# Sheet1.net
KiCad netlist of a schematic drawn in Altium Designer
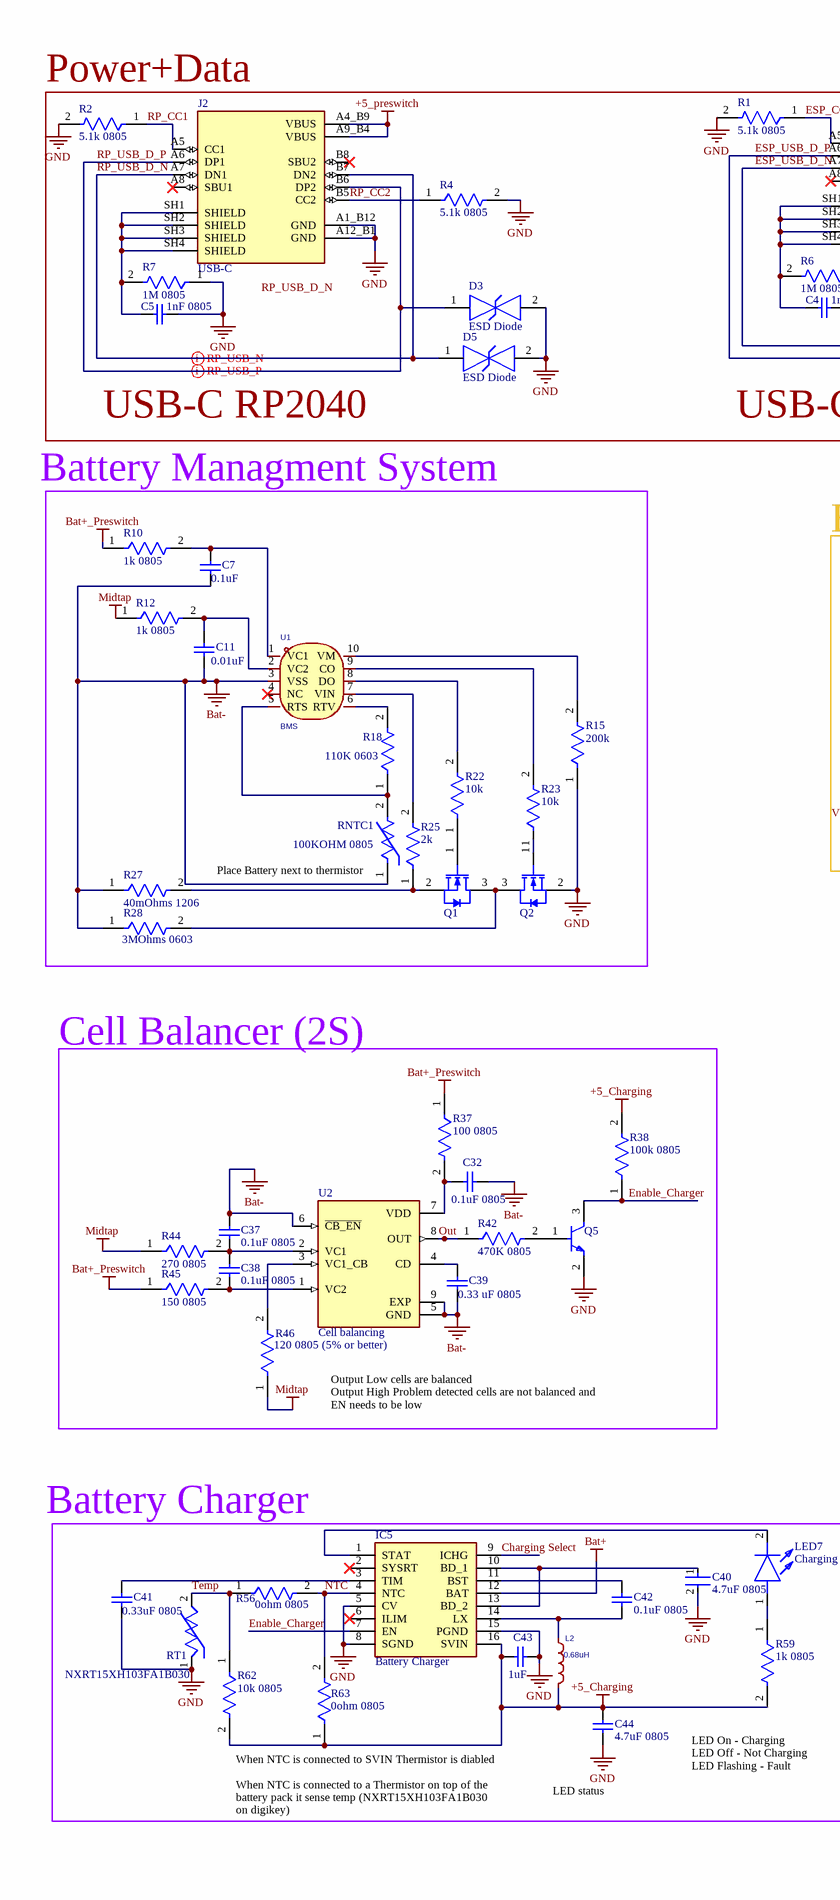
[diagram p0: Sheet1.SchDoc, left]
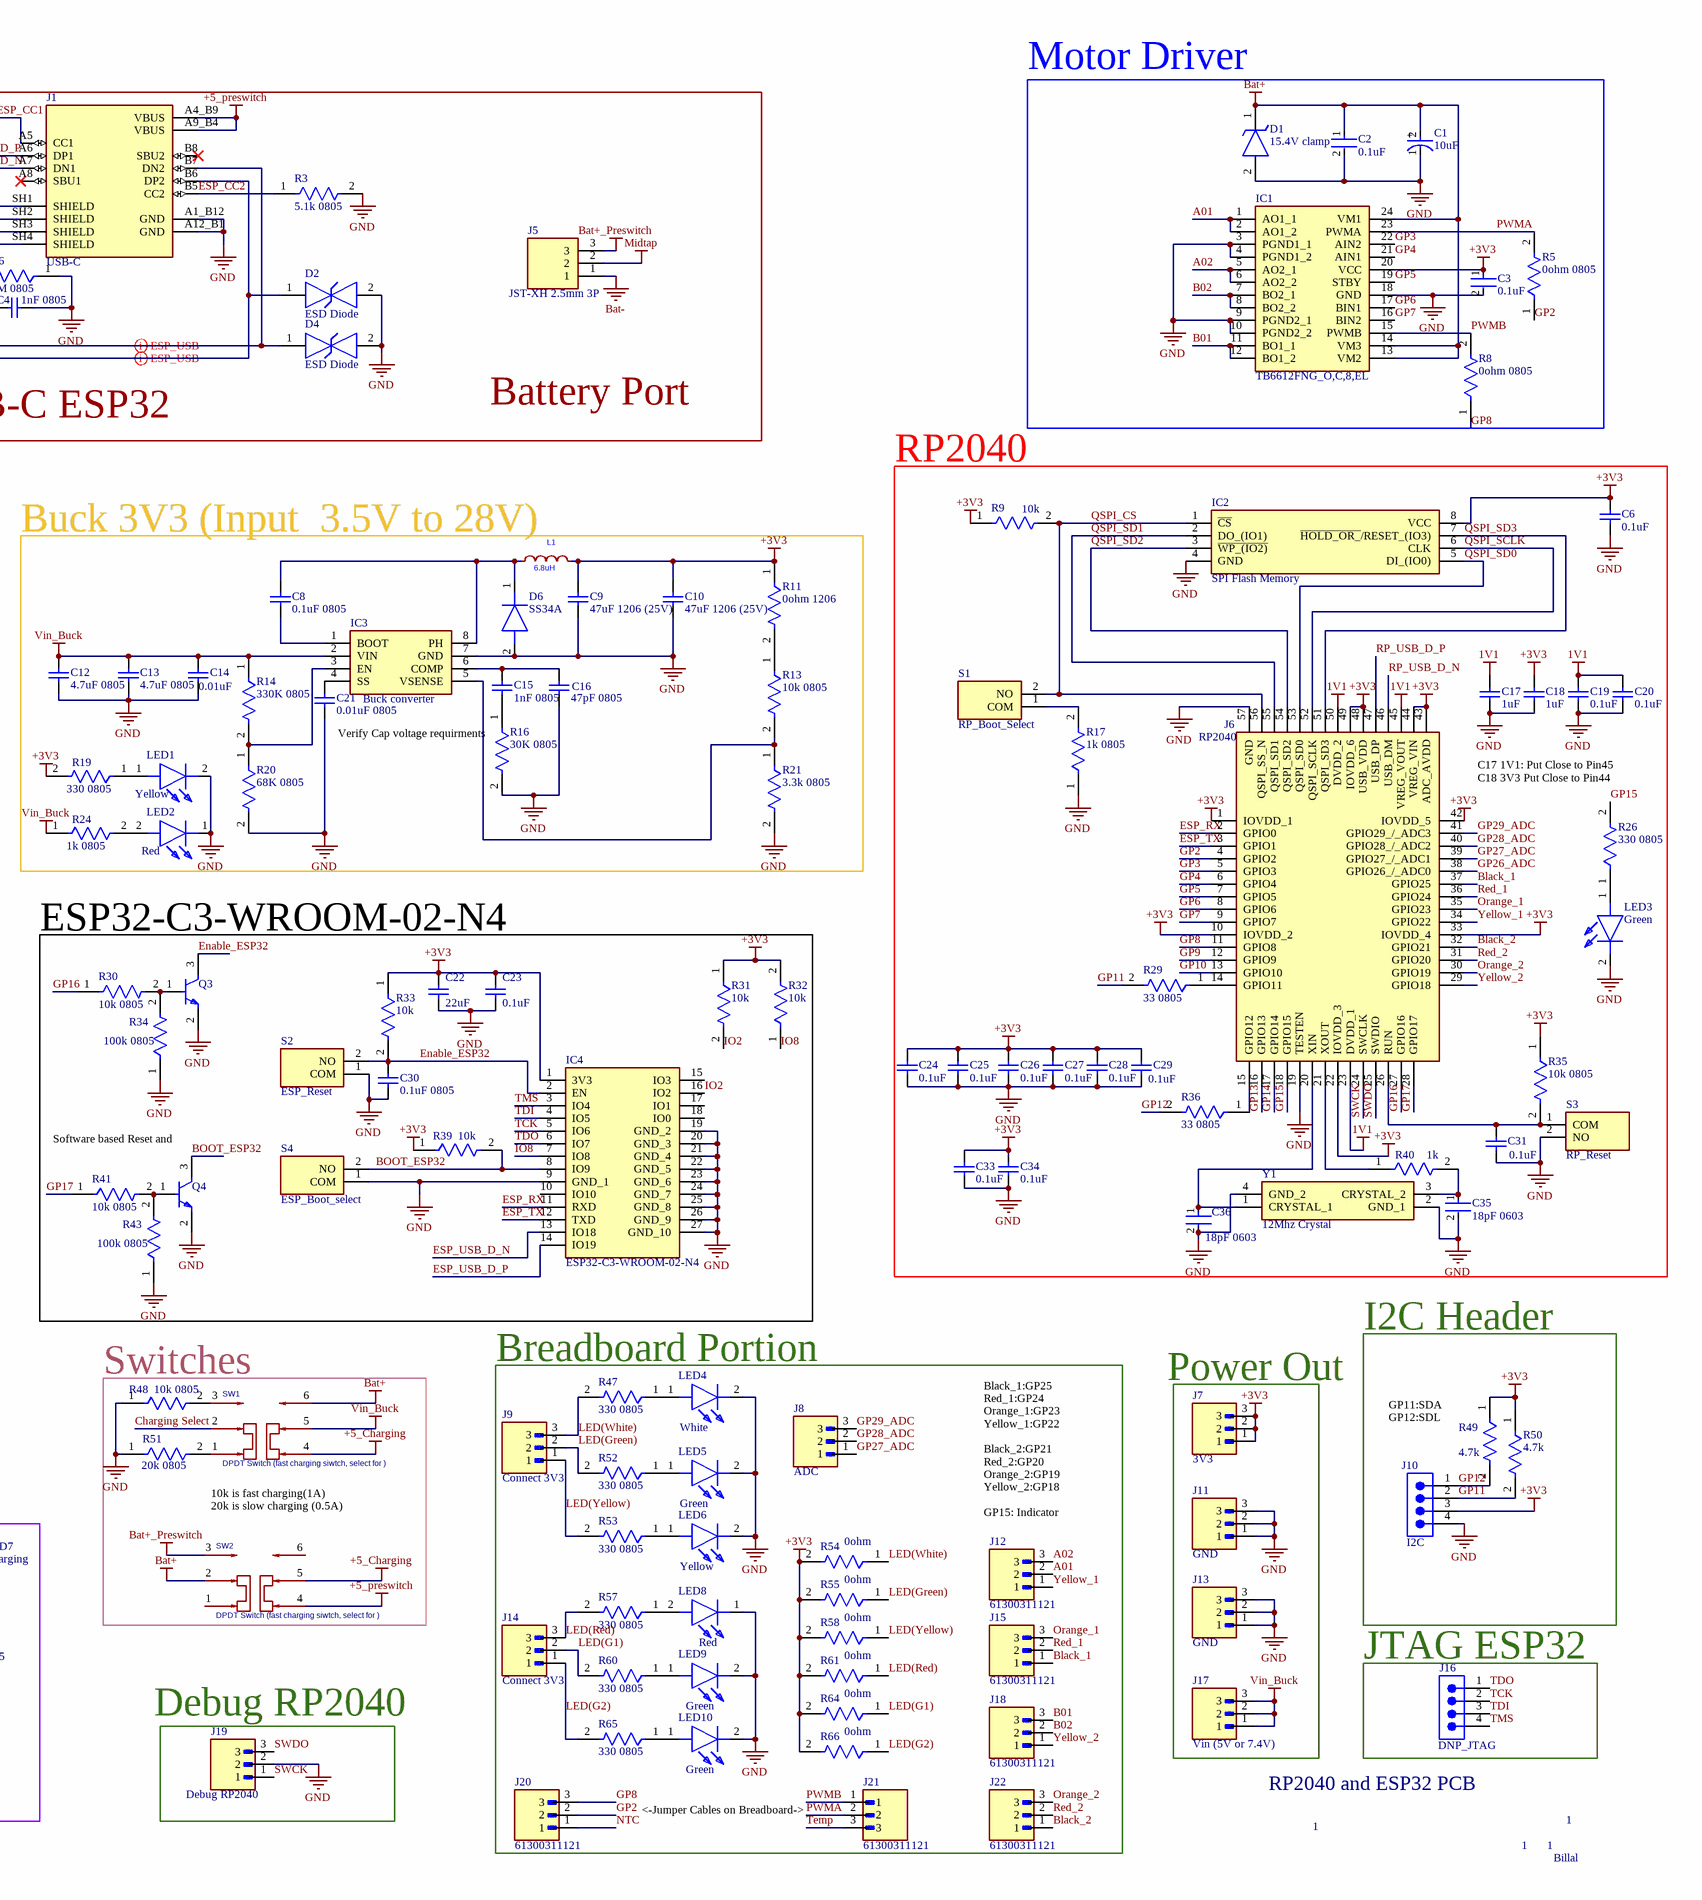
[diagram p1: Sheet1.SchDoc, right]

(export (version "E")
  (design (tool "Eeschema 10.0.6"))
  (components
    (comp (ref "C1")
      (value "10uF")
      (footprint "FP-TAJA-MFG")
      (description "C7171")
      (fields (field (name "VOLTAGE") "16V") (field (name "TOLERANCE") "10%"))
      (libsource (lib "Altium Content Vault") (part "203bc49f2ac43e59fd269a8c329ed05"))
    )
    (comp (ref "C2")
      (value "0.1uF")
      (footprint "FP-CL779-IPC_C")
      (description "C307331")
      (libsource (lib "Altium Content Vault") (part "b4654b650e69147ec39a6b967a45e02"))
    )
    (comp (ref "C3")
      (value "0.1uF")
      (footprint "FP-CL779-IPC_C")
      (description "C307331")
      (libsource (lib "Altium Content Vault") (part "b4654b650e69147ec39a6b967a45e02"))
    )
    (comp (ref "C4")
      (value "1nF 0805")
      (footprint "CAPC2013X94X50LL20T25")
      (description "C46653")
      (fields
        (field (name "PART NUMBER") "08051C102KAT4A")
        (field (name "MANUFACTURER") "AVX Interconnect / Elco")
      )
      (libsource (lib "Altium Content Vault") (part "CAP"))
    )
    (comp (ref "C5")
      (value "1nF 0805")
      (footprint "CAPC2013X94X50LL20T25")
      (description "C46653")
      (fields
        (field (name "PART NUMBER") "08051C102KAT4A")
        (field (name "MANUFACTURER") "AVX Interconnect / Elco")
      )
      (libsource (lib "Altium Content Vault") (part "CAP"))
    )
    (comp (ref "C6")
      (value "0.1uF")
      (footprint "CAPC2013X94X50LL20T25")
      (description "C28233")
      (fields
        (field (name "PART NUMBER") "08051C102KAT4A")
        (field (name "MANUFACTURER") "AVX Interconnect / Elco")
      )
      (libsource (lib "Altium Content Vault") (part "CAP"))
    )
    (comp (ref "C7")
      (value "0.1uF")
      (footprint "CAPC2013X94X50LL20T25")
      (description "C28233")
      (fields
        (field (name "PART NUMBER") "08051C102KAT4A")
        (field (name "MANUFACTURER") "AVX Interconnect / Elco")
      )
      (libsource (lib "Altium Content Vault") (part "CAP"))
    )
    (comp (ref "C8")
      (value "0.1uF 0805")
      (footprint "CAPC2013X94X50LL20T25")
      (description "C28233")
      (fields
        (field (name "PART NUMBER") "08051C102KAT4A")
        (field (name "MANUFACTURER") "AVX Interconnect / Elco")
      )
      (libsource (lib "Altium Content Vault") (part "CAP"))
    )
    (comp (ref "C9")
      (value "47uF 1206 (25V)")
      (footprint "CAPC1206(3216)190_N")
      (description "C6119973")
      (fields (field (name "TOLERANCE") "Â±20%"))
      (libsource (lib "Altium Content Vault") (part "CAP"))
    )
    (comp (ref "C10")
      (value "47uF 1206 (25V)")
      (footprint "CAPC1206(3216)190_N")
      (description "C6119973")
      (fields (field (name "TOLERANCE") "Â±20%"))
      (libsource (lib "Altium Content Vault") (part "CAP"))
    )
    (comp (ref "C11")
      (value "0.01uF")
      (footprint "CAPC2013X94X50LL20T25")
      (description "C1710")
      (fields
        (field (name "PART NUMBER") "08051C102KAT4A")
        (field (name "MANUFACTURER") "AVX Interconnect / Elco")
      )
      (libsource (lib "Altium Content Vault") (part "CAP"))
    )
    (comp (ref "C12")
      (value "4.7uF 0805")
      (footprint "CAPC2013X94X50LL20T25")
      (description "C1779")
      (fields
        (field (name "PART NUMBER") "08051C102KAT4A")
        (field (name "MANUFACTURER") "AVX Interconnect / Elco")
      )
      (libsource (lib "Altium Content Vault") (part "CAP"))
    )
    (comp (ref "C13")
      (value "4.7uF 0805")
      (footprint "CAPC2013X94X50LL20T25")
      (description "C1779")
      (fields
        (field (name "PART NUMBER") "08051C102KAT4A")
        (field (name "MANUFACTURER") "AVX Interconnect / Elco")
      )
      (libsource (lib "Altium Content Vault") (part "CAP"))
    )
    (comp (ref "C14")
      (value "0.01uF")
      (footprint "CAPC2013X94X50LL20T25")
      (description "C1710")
      (fields
        (field (name "PART NUMBER") "08051C102KAT4A")
        (field (name "MANUFACTURER") "AVX Interconnect / Elco")
      )
      (libsource (lib "Altium Content Vault") (part "CAP"))
    )
    (comp (ref "C15")
      (value "1nF 0805")
      (footprint "CAPC2013X94X50LL20T25")
      (description "C46653")
      (fields
        (field (name "PART NUMBER") "08051C102KAT4A")
        (field (name "MANUFACTURER") "AVX Interconnect / Elco")
      )
      (libsource (lib "Altium Content Vault") (part "CAP"))
    )
    (comp (ref "C16")
      (value "47pF 0805")
      (footprint "CAPC2013X94X50LL20T25")
      (description "C14857")
      (fields
        (field (name "PART NUMBER") "08051C102KAT4A")
        (field (name "MANUFACTURER") "AVX Interconnect / Elco")
      )
      (libsource (lib "Altium Content Vault") (part "CAP"))
    )
    (comp (ref "C17")
      (value "1uF")
      (footprint "CAPC2013X94X50LL20T25")
      (description "C28323\r\nPut Close to Pin45")
      (fields
        (field (name "PART NUMBER") "08051C102KAT4A")
        (field (name "MANUFACTURER") "AVX Interconnect / Elco")
      )
      (libsource (lib "Altium Content Vault") (part "CAP"))
    )
    (comp (ref "C18")
      (value "1uF")
      (footprint "CAPC2013X94X50LL20T25")
      (description "C28323\r\nPut Close to Pin44")
      (fields
        (field (name "PART NUMBER") "08051C102KAT4A")
        (field (name "MANUFACTURER") "AVX Interconnect / Elco")
      )
      (libsource (lib "Altium Content Vault") (part "CAP"))
    )
    (comp (ref "C19")
      (value "0.1uF")
      (footprint "CAPC2013X94X50LL20T25")
      (description "C28233")
      (fields
        (field (name "PART NUMBER") "08051C102KAT4A")
        (field (name "MANUFACTURER") "AVX Interconnect / Elco")
      )
      (libsource (lib "Altium Content Vault") (part "CAP"))
    )
    (comp (ref "C20")
      (value "0.1uF")
      (footprint "CAPC2013X94X50LL20T25")
      (description "C28233")
      (fields
        (field (name "PART NUMBER") "08051C102KAT4A")
        (field (name "MANUFACTURER") "AVX Interconnect / Elco")
      )
      (libsource (lib "Altium Content Vault") (part "CAP"))
    )
    (comp (ref "C21")
      (value "0.01uF 0805")
      (footprint "CAPC2013X94X50LL20T25")
      (description "C1710")
      (fields
        (field (name "PART NUMBER") "08051C102KAT4A")
        (field (name "MANUFACTURER") "AVX Interconnect / Elco")
      )
      (libsource (lib "Altium Content Vault") (part "CAP"))
    )
    (comp (ref "C22")
      (value "22uF")
      (footprint "CAPC2013X94X50LL20T25")
      (description "C45783")
      (fields
        (field (name "PART NUMBER") "08051C102KAT4A")
        (field (name "MANUFACTURER") "AVX Interconnect / Elco")
      )
      (libsource (lib "Altium Content Vault") (part "CAP"))
    )
    (comp (ref "C23")
      (value "0.1uF")
      (footprint "CAPC2013X94X50LL20T25")
      (description "C28233")
      (fields
        (field (name "PART NUMBER") "08051C102KAT4A")
        (field (name "MANUFACTURER") "AVX Interconnect / Elco")
      )
      (libsource (lib "Altium Content Vault") (part "CAP"))
    )
    (comp (ref "C24")
      (value "0.1uF")
      (footprint "CAPC2013X94X50LL20T25")
      (description "C28233")
      (fields
        (field (name "PART NUMBER") "08051C102KAT4A")
        (field (name "MANUFACTURER") "AVX Interconnect / Elco")
      )
      (libsource (lib "Altium Content Vault") (part "CAP"))
    )
    (comp (ref "C25")
      (value "0.1uF")
      (footprint "CAPC2013X94X50LL20T25")
      (description "C28233")
      (fields
        (field (name "PART NUMBER") "08051C102KAT4A")
        (field (name "MANUFACTURER") "AVX Interconnect / Elco")
      )
      (libsource (lib "Altium Content Vault") (part "CAP"))
    )
    (comp (ref "C26")
      (value "0.1uF")
      (footprint "CAPC2013X94X50LL20T25")
      (description "C28233")
      (fields
        (field (name "PART NUMBER") "08051C102KAT4A")
        (field (name "MANUFACTURER") "AVX Interconnect / Elco")
      )
      (libsource (lib "Altium Content Vault") (part "CAP"))
    )
    (comp (ref "C27")
      (value "0.1uF")
      (footprint "CAPC2013X94X50LL20T25")
      (description "C28233")
      (fields
        (field (name "PART NUMBER") "08051C102KAT4A")
        (field (name "MANUFACTURER") "AVX Interconnect / Elco")
      )
      (libsource (lib "Altium Content Vault") (part "CAP"))
    )
    (comp (ref "C28")
      (value "0.1uF")
      (footprint "CAPC2013X94X50LL20T25")
      (description "C28233")
      (fields
        (field (name "PART NUMBER") "08051C102KAT4A")
        (field (name "MANUFACTURER") "AVX Interconnect / Elco")
      )
      (libsource (lib "Altium Content Vault") (part "CAP"))
    )
    (comp (ref "C29")
      (value "0.1uF")
      (footprint "CAPC2013X94X50LL20T25")
      (description "C28233")
      (fields
        (field (name "PART NUMBER") "08051C102KAT4A")
        (field (name "MANUFACTURER") "AVX Interconnect / Elco")
      )
      (libsource (lib "Altium Content Vault") (part "CAP"))
    )
    (comp (ref "C30")
      (value "0.1uF 0805")
      (footprint "CAPC2013X94X50LL20T25")
      (description "C28233")
      (fields
        (field (name "PART NUMBER") "08051C102KAT4A")
        (field (name "MANUFACTURER") "AVX Interconnect / Elco")
      )
      (libsource (lib "Altium Content Vault") (part "CAP"))
    )
    (comp (ref "C31")
      (value "0.1uF")
      (footprint "CAPC2013X94X50LL20T25")
      (description "C28233")
      (fields
        (field (name "PART NUMBER") "08051C102KAT4A")
        (field (name "MANUFACTURER") "AVX Interconnect / Elco")
      )
      (libsource (lib "Altium Content Vault") (part "CAP"))
    )
    (comp (ref "C32")
      (value "0.1uF 0805")
      (footprint "CAPC2013X94X50LL20T25")
      (description "C28233")
      (fields
        (field (name "PART NUMBER") "08051C102KAT4A")
        (field (name "MANUFACTURER") "AVX Interconnect / Elco")
      )
      (libsource (lib "Altium Content Vault") (part "CAP"))
    )
    (comp (ref "C33")
      (value "0.1uF")
      (footprint "CAPC2013X94X50LL20T25")
      (description "C28233")
      (fields
        (field (name "PART NUMBER") "08051C102KAT4A")
        (field (name "MANUFACTURER") "AVX Interconnect / Elco")
      )
      (libsource (lib "Altium Content Vault") (part "CAP"))
    )
    (comp (ref "C34")
      (value "0.1uF")
      (footprint "CAPC2013X94X50LL20T25")
      (description "C28233")
      (fields
        (field (name "PART NUMBER") "08051C102KAT4A")
        (field (name "MANUFACTURER") "AVX Interconnect / Elco")
      )
      (libsource (lib "Altium Content Vault") (part "CAP"))
    )
    (comp (ref "C35")
      (value "18pF 0603")
      (footprint "FP-C0603C-CF-MFG")
      (description "C1647")
      (fields
        (field (name "TOLERANCE") "0.1")
        (field (name "OCTOPART") "https://octopart.com/c0603c180k4hactu-kemet-88725221")
      )
      (libsource (lib "Altium Content Vault") (part "b4654b650e69147ec39a6b967a45e02"))
    )
    (comp (ref "C36")
      (value "18pF 0603")
      (footprint "FP-C0603C-CF-MFG")
      (description "C1647")
      (fields
        (field (name "TOLERANCE") "0.1")
        (field (name "OCTOPART") "https://octopart.com/c0603c180k4hactu-kemet-88725221")
      )
      (libsource (lib "Altium Content Vault") (part "b4654b650e69147ec39a6b967a45e02"))
    )
    (comp (ref "C37")
      (value "0.1uF 0805")
      (footprint "CAPC2013X94X50LL20T25")
      (description "C28233")
      (fields
        (field (name "PART NUMBER") "08051C102KAT4A")
        (field (name "MANUFACTURER") "AVX Interconnect / Elco")
      )
      (libsource (lib "Altium Content Vault") (part "CAP"))
    )
    (comp (ref "C38")
      (value "0.1uF 0805")
      (footprint "CAPC2013X94X50LL20T25")
      (description "C28233")
      (fields
        (field (name "PART NUMBER") "08051C102KAT4A")
        (field (name "MANUFACTURER") "AVX Interconnect / Elco")
      )
      (libsource (lib "Altium Content Vault") (part "CAP"))
    )
    (comp (ref "C39")
      (value "0.33 uF 0805")
      (footprint "CAPC2013X94X50LL20T25")
      (description "C1740")
      (fields
        (field (name "PART NUMBER") "08051C102KAT4A")
        (field (name "MANUFACTURER") "AVX Interconnect / Elco")
      )
      (libsource (lib "Altium Content Vault") (part "CAP"))
    )
    (comp (ref "C40")
      (value "4.7uF 0805")
      (footprint "FP-CC0805-0_85-MFG")
      (description "C1779")
      (fields (field (name "TOLERANCE") "0.1") (field (name "MANUFACTURER") "Yageo"))
      (libsource (lib "Altium Content Vault") (part "11868f565c42a9108669ba33697ecf6"))
    )
    (comp (ref "C41")
      (value "0.33uF 0805")
      (footprint "CAPC2013X94X50LL20T25")
      (description "C1740")
      (fields
        (field (name "PART NUMBER") "08051C102KAT4A")
        (field (name "MANUFACTURER") "AVX Interconnect / Elco")
      )
      (libsource (lib "Altium Content Vault") (part "CAP"))
    )
    (comp (ref "C42")
      (value "0.1uF 0805")
      (footprint "CAPC2013X94X50LL20T25")
      (description "C28233")
      (fields
        (field (name "PART NUMBER") "08051C102KAT4A")
        (field (name "MANUFACTURER") "AVX Interconnect / Elco")
      )
      (libsource (lib "Altium Content Vault") (part "CAP"))
    )
    (comp (ref "C43")
      (value "1uF")
      (footprint "CAPC2013X94X50LL20T25")
      (description "C28323")
      (fields
        (field (name "PART NUMBER") "08051C102KAT4A")
        (field (name "MANUFACTURER") "AVX Interconnect / Elco")
      )
      (libsource (lib "Altium Content Vault") (part "CAP"))
    )
    (comp (ref "C44")
      (value "4.7uF 0805")
      (footprint "CAPC2013X94X50LL20T25")
      (description "C1779")
      (fields
        (field (name "PART NUMBER") "08051C102KAT4A")
        (field (name "MANUFACTURER") "AVX Interconnect / Elco")
      )
      (libsource (lib "Altium Content Vault") (part "CAP"))
    )
    (comp (ref "D1")
      (value "15.4V clamp")
      (footprint "SamacSys:DIOM5437X260N")
      (description "C707989")
      (fields (field (name "MANUFACTURER_PART_NUMBER") "SMBJ9.0A"))
      (libsource (lib "*") (part "SMBJ9.0A"))
    )
    (comp (ref "D2")
      (value "ESD Diode")
      (footprint "FP-GG0402-MFG")
      (description "C10662")
      (fields
        (field (name "MANUFACTURER PART NUMBER") "GG040205100N2P")
        (field (name "OCTOPART") "https://octopart.com/gg040205100n2p-avx-81066081")
      )
      (libsource (lib "Altium Content Vault") (part "69d1c9d986d6c23c51904d32b7d60a2"))
    )
    (comp (ref "D3")
      (value "ESD Diode")
      (footprint "FP-GG0402-MFG")
      (description "C10662")
      (fields
        (field (name "MANUFACTURER PART NUMBER") "GG040205100N2P")
        (field (name "OCTOPART") "https://octopart.com/gg040205100n2p-avx-81066081")
      )
      (libsource (lib "Altium Content Vault") (part "69d1c9d986d6c23c51904d32b7d60a2"))
    )
    (comp (ref "D4")
      (value "ESD Diode")
      (footprint "FP-GG0402-MFG")
      (description "C10662")
      (fields
        (field (name "MANUFACTURER PART NUMBER") "GG040205100N2P")
        (field (name "OCTOPART") "https://octopart.com/gg040205100n2p-avx-81066081")
      )
      (libsource (lib "Altium Content Vault") (part "69d1c9d986d6c23c51904d32b7d60a2"))
    )
    (comp (ref "D5")
      (value "ESD Diode")
      (footprint "FP-GG0402-MFG")
      (description "C10662")
      (fields
        (field (name "MANUFACTURER PART NUMBER") "GG040205100N2P")
        (field (name "OCTOPART") "https://octopart.com/gg040205100n2p-avx-81066081")
      )
      (libsource (lib "Altium Content Vault") (part "69d1c9d986d6c23c51904d32b7d60a2"))
    )
    (comp (ref "D6")
      (value "SS34A")
      (footprint "SamacSys:DIOM5026X262N")
      (description "C8678")
      (libsource (lib "*") (part "SS34A"))
    )
    (comp (ref "IC1")
      (value "TB6612FNG_O,C,8,EL")
      (footprint "SamacSys:SOP65P760X160-24N")
      (description "C88224")
      (fields
        (field (name "MANUFACTURER_PART_NUMBER") "TB6612FNG(O,C,8,EL")
        (field (name "MOUSER PART NUMBER") "757-TB6612FNGOC8EL")
      )
      (libsource (lib "*") (part "TB6612FNG_O,C,8,EL"))
    )
    (comp (ref "IC2")
      (value "SPI Flash Memory")
      (footprint "SamacSys:SOIC127P790X216-8N")
      (description "C131025")
      (fields
        (field (name "MANUFACTURER_PART_NUMBER") "W25Q16JVSSIQ TR")
        (field (name "MOUSER PART NUMBER") "454-W25Q16JVSSIQTR")
      )
      (libsource (lib "*") (part "W25Q16JVSSIQ_TR"))
    )
    (comp (ref "IC3")
      (value "Buck converter")
      (footprint "SamacSys:SOIC127P600X175-8N")
      (description "C9865")
      (fields
        (field (name "MANUFACTURER_PART_NUMBER") "TPS54331D")
        (field (name "MOUSER PART NUMBER") "595-TPS54331D")
      )
      (libsource (lib "*") (part "TPS54331D"))
    )
    (comp (ref "IC4")
      (value "ESP32-C3-WROOM-02-N4")
      (footprint "SamacSys:ESP32C3WROOM02N4")
      (description "C2934560")
      (fields (field (name "MOUSER PART NUMBER") "356-ESP32C3WROOM02N4"))
      (libsource (lib "*") (part "ESP32-C3-WROOM-02-N4"))
    )
    (comp (ref "IC5")
      (value "Battery Charger")
      (footprint "SamacSys:SY6982CQDC")
      (description "C7435940")
      (fields (field (name "MANUFACTURER_PART_NUMBER") "SY6982CQDC"))
      (libsource (lib "*") (part "SY6982CQDC"))
    )
    (comp (ref "J1")
      (value "USB-C")
      (footprint "KINGHELM_KH-TYPE-C-16P")
      (description "C2765186")
      (fields (field (name "MF") "kinghelm") (field (name "MP") "KH-TYPE-C-16P"))
      (libsource (lib "Schlib1") (part "KH-TYPE-C-16P"))
    )
    (comp (ref "J2")
      (value "USB-C")
      (footprint "KINGHELM_KH-TYPE-C-16P")
      (description "C2765186")
      (fields (field (name "MF") "kinghelm") (field (name "MP") "KH-TYPE-C-16P"))
      (libsource (lib "Schlib1") (part "KH-TYPE-C-16P"))
    )
    (comp (ref "J5")
      (value "JST-XH 2.5mm 3P")
      (footprint "SamacSys:B3BXHALFSN")
      (description "C144394")
      (fields
        (field (name "MANUFACTURER_PART_NUMBER") "B3B-XH-A(LF)(SN)")
        (field (name "MOUSER PART NUMBER") "306-B3BXHALFSNP")
      )
      (libsource (lib "*") (part "B3B-XH-A_LF__SN_"))
    )
    (comp (ref "J6")
      (value "RP2040")
      (footprint "SamacSys:SC091413")
      (description "C2040")
      (fields
        (field (name "MANUFACTURER_PART_NUMBER") "SC0914(13)")
        (field (name "MOUSER PART NUMBER") "358-SC091413")
      )
      (libsource (lib "*") (part "SC0914_13_"))
    )
    (comp (ref "J7")
      (value "3V3")
      (footprint "WURTH_61300311121")
      (description "C52016391")
      (fields (field (name "MP") "61300311121"))
      (libsource (lib "Schlib1") (part "61300311121"))
    )
    (comp (ref "J8")
      (value "ADC")
      (footprint "WURTH_61300311121")
      (description "C52016391")
      (fields (field (name "MP") "61300311121"))
      (libsource (lib "Schlib1") (part "61300311121"))
    )
    (comp (ref "J9")
      (value "Connect 3V3")
      (footprint "WURTH_61300311121")
      (description "C52016391")
      (fields (field (name "MP") "61300311121"))
      (libsource (lib "Schlib1") (part "61300311121"))
    )
    (comp (ref "J10")
      (value "I2C")
      (footprint "SMTC-TSW-104-08-X-S")
      (description "0.025\" SQ Post Header, Through-hole, Vertical, -55 to 125 degC, 2.54 mm Pitch, 4-Pin, Male, RoHS")
      (fields (field (name "MANUFACTURER") "Samtec") (field (name "PARTNUMBER") "TSW-104-08-G-S"))
      (libsource (lib "Altium Content Vault") (part "SMTC-TSW-104-08-X-S"))
    )
    (comp (ref "J11")
      (value "GND")
      (footprint "WURTH_61300311121")
      (description "C52016391")
      (fields (field (name "MP") "61300311121"))
      (libsource (lib "Schlib1") (part "61300311121"))
    )
    (comp (ref "J12")
      (value "61300311121")
      (footprint "WURTH_61300311121")
      (description "C52016391")
      (libsource (lib "Schlib1") (part "61300311121"))
    )
    (comp (ref "J13")
      (value "GND")
      (footprint "WURTH_61300311121")
      (description "C52016391")
      (fields (field (name "MP") "61300311121"))
      (libsource (lib "Schlib1") (part "61300311121"))
    )
    (comp (ref "J14")
      (value "Connect 3V3")
      (footprint "WURTH_61300311121")
      (description "C52016391")
      (fields (field (name "MP") "61300311121"))
      (libsource (lib "Schlib1") (part "61300311121"))
    )
    (comp (ref "J15")
      (value "61300311121")
      (footprint "WURTH_61300311121")
      (description "C52016391")
      (libsource (lib "Schlib1") (part "61300311121"))
    )
    (comp (ref "J16")
      (value "DNP_JTAG")
      (footprint "SMTC-TSW-104-08-X-S")
      (description "0.025\" SQ Post Header, Through-hole, Vertical, -55 to 125 degC, 2.54 mm Pitch, 4-Pin, Male, RoHS")
      (fields (field (name "MANUFACTURER") "Samtec") (field (name "PARTNUMBER") "TSW-104-08-G-S"))
      (libsource (lib "Altium Content Vault") (part "SMTC-TSW-104-08-X-S"))
    )
    (comp (ref "J17")
      (value "Vin (5V or 7.4V)")
      (footprint "WURTH_61300311121")
      (description "C52016391")
      (fields (field (name "MP") "61300311121"))
      (libsource (lib "Schlib1") (part "61300311121"))
    )
    (comp (ref "J18")
      (value "61300311121")
      (footprint "WURTH_61300311121")
      (description "C52016391")
      (libsource (lib "Schlib1") (part "61300311121"))
    )
    (comp (ref "J19")
      (value "Debug RP2040")
      (footprint "WURTH_61300311121")
      (description "C52016391")
      (fields (field (name "MP") "61300311121"))
      (libsource (lib "Schlib1") (part "61300311121"))
    )
    (comp (ref "J20")
      (value "61300311121")
      (footprint "WURTH_61300311121")
      (description "C52016391")
      (libsource (lib "Schlib1") (part "61300311121"))
    )
    (comp (ref "J21")
      (value "61300311121")
      (footprint "WURTH_61300311121")
      (description "C52016391")
      (libsource (lib "") (part "61300311121_1"))
    )
    (comp (ref "J22")
      (value "61300311121")
      (footprint "WURTH_61300311121")
      (description "C52016391")
      (libsource (lib "Schlib1") (part "61300311121"))
    )
    (comp (ref "L1")
      (value "6.8uH")
      (footprint "IND-SMD_L7.0-W6.6")
      (description "C167221")
      (fields (field (name "MANUFACTURER") "cjiang(长江微电)") (field (name "MANUFACTURER PART") "FXL0630-6R8-M"))
      (libsource (lib "Schlib1") (part "FXL0630-6R8-M"))
    )
    (comp (ref "L2")
      (value "0.68uH")
      (footprint "IND-SMD_L2.5-W2.0")
      (description "C492726")
      (fields
        (field (name "MANUFACTURER") "Sumida(胜美达)")
        (field (name "MANUFACTURER PART") "252012CDMCDDS-R68MC")
      )
      (libsource (lib "Schlib1") (part "252012CDMCDDS-R68MC"))
    )
    (comp (ref "LED1")
      (value "Yellow")
      (footprint "SamacSys:KT0805G")
      (description "C2296")
      (fields (field (name "MANUFACTURER_PART_NUMBER") "KT-0805G"))
      (libsource (lib "*") (part "KT-0805G"))
    )
    (comp (ref "LED2")
      (value "Red")
      (footprint "SamacSys:LEDC1608X70N")
      (description "C2286")
      (fields (field (name "MANUFACTURER_PART_NUMBER") "KT-0603R"))
      (libsource (lib "*") (part "KT-0603R"))
    )
    (comp (ref "LED3")
      (value "Green")
      (footprint "SamacSys:KT0805G")
      (description "C2297")
      (fields (field (name "MANUFACTURER_PART_NUMBER") "KT-0805G"))
      (libsource (lib "*") (part "KT-0805G"))
    )
    (comp (ref "LED4")
      (value "White")
      (footprint "SamacSys:KT0805G")
      (description "C34499")
      (fields (field (name "MANUFACTURER_PART_NUMBER") "KT-0805G"))
      (libsource (lib "*") (part "KT-0805G"))
    )
    (comp (ref "LED5")
      (value "Green")
      (footprint "SamacSys:KT0805G")
      (description "C2297")
      (fields (field (name "MANUFACTURER_PART_NUMBER") "KT-0805G"))
      (libsource (lib "*") (part "KT-0805G"))
    )
    (comp (ref "LED6")
      (value "Yellow")
      (footprint "SamacSys:KT0805G")
      (description "C2296")
      (fields (field (name "MANUFACTURER_PART_NUMBER") "KT-0805G"))
      (libsource (lib "*") (part "KT-0805G"))
    )
    (comp (ref "LED7")
      (value "Charging")
      (footprint "SamacSys:KT0805G")
      (description "C2297")
      (fields (field (name "MANUFACTURER_PART_NUMBER") "KT-0805G"))
      (libsource (lib "*") (part "KT-0805G"))
    )
    (comp (ref "LED8")
      (value "Red")
      (footprint "SamacSys:LEDC1608X70N")
      (description "C2286")
      (fields (field (name "MANUFACTURER_PART_NUMBER") "KT-0603R"))
      (libsource (lib "*") (part "KT-0603R"))
    )
    (comp (ref "LED9")
      (value "Green")
      (footprint "SamacSys:KT0805G")
      (description "C2297")
      (fields (field (name "MANUFACTURER_PART_NUMBER") "KT-0805G"))
      (libsource (lib "*") (part "KT-0805G"))
    )
    (comp (ref "LED10")
      (value "Green")
      (footprint "SamacSys:KT0805G")
      (description "C2297")
      (fields (field (name "MANUFACTURER_PART_NUMBER") "KT-0805G"))
      (libsource (lib "*") (part "KT-0805G"))
    )
    (comp (ref "Q1")
      (value "Discharge Protection")
      (footprint "ONSC-SOT-23-3-318-08_V")
      (description "C20917")
      (fields (field (name "MANUFACTURER") "On Semiconductor") (field (name "PARTNUMBER") "2N7002LT1G"))
      (libsource (lib "Altium Content Vault") (part "ONSC-NMOS-G1S2D3-3"))
    )
    (comp (ref "Q2")
      (value "Charge Protection")
      (footprint "ONSC-SOT-23-3-318-08_V")
      (description "C20917")
      (fields (field (name "MANUFACTURER") "On Semiconductor") (field (name "PARTNUMBER") "2N7002LT1G"))
      (libsource (lib "Altium Content Vault") (part "ONSC-NMOS-G1S2D3-3"))
    )
    (comp (ref "Q3")
      (value "MMBT3904-7-F")
      (footprint "FP-SOT23-IPC_A")
      (description "C364310")
      (libsource (lib "Altium Content Vault") (part "b44e953556f554d0102664c7d152cb4"))
    )
    (comp (ref "Q4")
      (value "MMBT3904-7-F")
      (footprint "FP-SOT23-IPC_A")
      (description "C364310")
      (libsource (lib "Altium Content Vault") (part "b44e953556f554d0102664c7d152cb4"))
    )
    (comp (ref "Q5")
      (value "MMBT3904-7-F")
      (footprint "FP-SOT23-IPC_A")
      (description "C364310")
      (libsource (lib "Altium Content Vault") (part "b44e953556f554d0102664c7d152cb4"))
    )
    (comp (ref "R1")
      (value "5.1k 0805")
      (footprint "FP-RN73R2A-IPC_C")
      (description "C27834")
      (libsource (lib "Altium Content Vault") (part "1029c3af85768c4190bb7ad29bc67b5"))
    )
    (comp (ref "R2")
      (value "5.1k 0805")
      (footprint "FP-RN73R2A-IPC_C")
      (description "C27834")
      (libsource (lib "Altium Content Vault") (part "1029c3af85768c4190bb7ad29bc67b5"))
    )
    (comp (ref "R3")
      (value "5.1k 0805")
      (footprint "FP-RN73R2A-IPC_C")
      (description "C27834")
      (libsource (lib "Altium Content Vault") (part "1029c3af85768c4190bb7ad29bc67b5"))
    )
    (comp (ref "R4")
      (value "5.1k 0805")
      (footprint "FP-RN73R2A-IPC_C")
      (description "C27834")
      (libsource (lib "Altium Content Vault") (part "1029c3af85768c4190bb7ad29bc67b5"))
    )
    (comp (ref "R5")
      (value "0ohm 0805")
      (footprint "FP-HCJ0805-MFG")
      (description "C17477")
      (libsource (lib "Altium Content Vault") (part "1029c3af85768c4190bb7ad29bc67b5"))
    )
    (comp (ref "R6")
      (value "1M 0805")
      (footprint "FP-RN73R2A-IPC_C")
      (description "C17514")
      (libsource (lib "Altium Content Vault") (part "1029c3af85768c4190bb7ad29bc67b5"))
    )
    (comp (ref "R7")
      (value "1M 0805")
      (footprint "FP-RN73R2A-IPC_C")
      (description "C17514")
      (libsource (lib "Altium Content Vault") (part "1029c3af85768c4190bb7ad29bc67b5"))
    )
    (comp (ref "R8")
      (value "0ohm 0805")
      (footprint "FP-HCJ0805-MFG")
      (description "C17477")
      (libsource (lib "Altium Content Vault") (part "1029c3af85768c4190bb7ad29bc67b5"))
    )
    (comp (ref "R9")
      (value "10k")
      (footprint "FP-RN73R2A-IPC_C")
      (description "C17414")
      (libsource (lib "Altium Content Vault") (part "1029c3af85768c4190bb7ad29bc67b5"))
    )
    (comp (ref "R10")
      (value "1k 0805")
      (footprint "FP-RN73R2A-IPC_C")
      (description "C1015")
      (libsource (lib "Altium Content Vault") (part "1029c3af85768c4190bb7ad29bc67b5"))
    )
    (comp (ref "R11")
      (value "0ohm 1206")
      (footprint "FP-HCJ1206-MFG")
      (description "C17888")
      (libsource (lib "Altium Content Vault") (part "1029c3af85768c4190bb7ad29bc67b5"))
    )
    (comp (ref "R12")
      (value "1k 0805")
      (footprint "FP-RN73R2A-IPC_C")
      (description "C1015")
      (libsource (lib "Altium Content Vault") (part "1029c3af85768c4190bb7ad29bc67b5"))
    )
    (comp (ref "R13")
      (value "10k 0805")
      (footprint "FP-RN73R2A-IPC_C")
      (description "C17414")
      (libsource (lib "Altium Content Vault") (part "1029c3af85768c4190bb7ad29bc67b5"))
    )
    (comp (ref "R14")
      (value "330K 0805")
      (footprint "FP-RN73R2A-IPC_C")
      (description "C17629")
      (libsource (lib "Altium Content Vault") (part "1029c3af85768c4190bb7ad29bc67b5"))
    )
    (comp (ref "R15")
      (value "200k")
      (footprint "FP-RN73R2A-IPC_C")
      (description "C17539")
      (libsource (lib "Altium Content Vault") (part "1029c3af85768c4190bb7ad29bc67b5"))
    )
    (comp (ref "R16")
      (value "30K 0805")
      (footprint "FP-RN73R2A-IPC_C")
      (description "C17621")
      (libsource (lib "Altium Content Vault") (part "1029c3af85768c4190bb7ad29bc67b5"))
    )
    (comp (ref "R17")
      (value "1k 0805")
      (footprint "FP-RN73R2A-IPC_C")
      (description "C1015")
      (libsource (lib "Altium Content Vault") (part "1029c3af85768c4190bb7ad29bc67b5"))
    )
    (comp (ref "R18")
      (value "110K 0603")
      (footprint "FP-RMCF0603-IPC_C")
      (description "C25805")
      (fields (field (name "TOLERANCE") "5%"))
      (libsource (lib "Altium Content Vault") (part "1029c3af85768c4190bb7ad29bc67b5"))
    )
    (comp (ref "R19")
      (value "330 0805")
      (footprint "FP-RN73R2A-IPC_C")
      (description "C17630")
      (libsource (lib "Altium Content Vault") (part "1029c3af85768c4190bb7ad29bc67b5"))
    )
    (comp (ref "R20")
      (value "68K 0805")
      (footprint "FP-RN73R2A-IPC_C")
      (description "C17801")
      (libsource (lib "Altium Content Vault") (part "1029c3af85768c4190bb7ad29bc67b5"))
    )
    (comp (ref "R21")
      (value "3.3k 0805")
      (footprint "FP-RN73R2A-IPC_C")
      (description "C26010")
      (libsource (lib "Altium Content Vault") (part "1029c3af85768c4190bb7ad29bc67b5"))
    )
    (comp (ref "R22")
      (value "10k")
      (footprint "FP-RN73R2A-IPC_C")
      (description "C17414")
      (libsource (lib "Altium Content Vault") (part "1029c3af85768c4190bb7ad29bc67b5"))
    )
    (comp (ref "R23")
      (value "10k")
      (footprint "FP-RN73R2A-IPC_C")
      (description "C17414")
      (libsource (lib "Altium Content Vault") (part "1029c3af85768c4190bb7ad29bc67b5"))
    )
    (comp (ref "R24")
      (value "1k 0805")
      (footprint "FP-RN73R2A-IPC_C")
      (description "C1015")
      (libsource (lib "Altium Content Vault") (part "1029c3af85768c4190bb7ad29bc67b5"))
    )
    (comp (ref "R25")
      (value "2k")
      (footprint "FP-RN73R2A-IPC_C")
      (description "C17604")
      (libsource (lib "Altium Content Vault") (part "1029c3af85768c4190bb7ad29bc67b5"))
    )
    (comp (ref "R26")
      (value "330 0805")
      (footprint "FP-RN73R2A-IPC_C")
      (description "C17630")
      (libsource (lib "Altium Content Vault") (part "1029c3af85768c4190bb7ad29bc67b5"))
    )
    (comp (ref "R27")
      (value "40mOhms 1206")
      (footprint "FP-WSL1206-0_508-MFG")
      (description "C49654479")
      (fields (field (name "TOLERANCE") "1%"))
      (libsource (lib "Altium Content Vault") (part "1029c3af85768c4190bb7ad29bc67b5"))
    )
    (comp (ref "R28")
      (value "3MOhms 0603")
      (footprint "FP-AC0603-MFG")
      (description "C23156")
      (fields (field (name "TOLERANCE") "1%"))
      (libsource (lib "Altium Content Vault") (part "1029c3af85768c4190bb7ad29bc67b5"))
    )
    (comp (ref "R29")
      (value "33 0805")
      (footprint "FP-RN73R2A-IPC_C")
      (description "C17634")
      (libsource (lib "Altium Content Vault") (part "1029c3af85768c4190bb7ad29bc67b5"))
    )
    (comp (ref "R30")
      (value "10k 0805")
      (footprint "FP-RN73R2A-IPC_C")
      (description "C17414")
      (libsource (lib "Altium Content Vault") (part "1029c3af85768c4190bb7ad29bc67b5"))
    )
    (comp (ref "R31")
      (value "10k")
      (footprint "FP-RN73R2A-IPC_C")
      (description "C17414")
      (libsource (lib "Altium Content Vault") (part "1029c3af85768c4190bb7ad29bc67b5"))
    )
    (comp (ref "R32")
      (value "10k")
      (footprint "FP-RN73R2A-IPC_C")
      (description "C17414")
      (libsource (lib "Altium Content Vault") (part "1029c3af85768c4190bb7ad29bc67b5"))
    )
    (comp (ref "R33")
      (value "10k")
      (footprint "FP-RN73R2A-IPC_C")
      (description "C17414")
      (libsource (lib "Altium Content Vault") (part "1029c3af85768c4190bb7ad29bc67b5"))
    )
    (comp (ref "R34")
      (value "100k 0805")
      (footprint "FP-RN73R2A-IPC_C")
      (description "C149504")
      (libsource (lib "Altium Content Vault") (part "1029c3af85768c4190bb7ad29bc67b5"))
    )
    (comp (ref "R35")
      (value "10k 0805")
      (footprint "FP-RN73R2A-IPC_C")
      (description "C17414")
      (libsource (lib "Altium Content Vault") (part "1029c3af85768c4190bb7ad29bc67b5"))
    )
    (comp (ref "R36")
      (value "33 0805")
      (footprint "FP-RN73R2A-IPC_C")
      (description "C17634")
      (libsource (lib "Altium Content Vault") (part "1029c3af85768c4190bb7ad29bc67b5"))
    )
    (comp (ref "R37")
      (value "100 0805")
      (footprint "FP-RN73R2A-IPC_C")
      (description "C17408")
      (libsource (lib "Altium Content Vault") (part "1029c3af85768c4190bb7ad29bc67b5"))
    )
    (comp (ref "R38")
      (value "100k 0805")
      (footprint "FP-RN73R2A-IPC_C")
      (description "C149504")
      (libsource (lib "Altium Content Vault") (part "1029c3af85768c4190bb7ad29bc67b5"))
    )
    (comp (ref "R39")
      (value "10k")
      (footprint "FP-RN73R2A-IPC_C")
      (description "C17414")
      (libsource (lib "Altium Content Vault") (part "1029c3af85768c4190bb7ad29bc67b5"))
    )
    (comp (ref "R40")
      (value "1k")
      (footprint "FP-RN73R2A-IPC_C")
      (description "C1015")
      (libsource (lib "Altium Content Vault") (part "1029c3af85768c4190bb7ad29bc67b5"))
    )
    (comp (ref "R41")
      (value "10k 0805")
      (footprint "FP-RN73R2A-IPC_C")
      (description "C17414")
      (libsource (lib "Altium Content Vault") (part "1029c3af85768c4190bb7ad29bc67b5"))
    )
    (comp (ref "R42")
      (value "470K 0805")
      (footprint "FP-RN73R2A-IPC_C")
      (description "C17709")
      (libsource (lib "Altium Content Vault") (part "1029c3af85768c4190bb7ad29bc67b5"))
    )
    (comp (ref "R43")
      (value "100k 0805")
      (footprint "FP-RN73R2A-IPC_C")
      (description "C149504")
      (libsource (lib "Altium Content Vault") (part "1029c3af85768c4190bb7ad29bc67b5"))
    )
    (comp (ref "R44")
      (value "270 0805")
      (footprint "FP-RN73R2A-IPC_C")
      (description "C17590")
      (libsource (lib "Altium Content Vault") (part "1029c3af85768c4190bb7ad29bc67b5"))
    )
    (comp (ref "R45")
      (value "150 0805")
      (footprint "FP-RN73R2A-IPC_C")
      (description "C17471")
      (libsource (lib "Altium Content Vault") (part "1029c3af85768c4190bb7ad29bc67b5"))
    )
    (comp (ref "R46")
      (value "120 0805 (5% or better)")
      (footprint "FP-RN73R2A-IPC_C")
      (description "C17437")
      (libsource (lib "Altium Content Vault") (part "1029c3af85768c4190bb7ad29bc67b5"))
    )
    (comp (ref "R47")
      (value "330 0805")
      (footprint "FP-RN73R2A-IPC_C")
      (description "C17630")
      (libsource (lib "Altium Content Vault") (part "1029c3af85768c4190bb7ad29bc67b5"))
    )
    (comp (ref "R48")
      (value "10k 0805")
      (footprint "FP-RN73R2A-IPC_C")
      (description "C17414")
      (libsource (lib "Altium Content Vault") (part "1029c3af85768c4190bb7ad29bc67b5"))
    )
    (comp (ref "R49")
      (value "4.7k")
      (footprint "FP-RN73R2A-IPC_C")
      (description "C17673")
      (libsource (lib "Altium Content Vault") (part "1029c3af85768c4190bb7ad29bc67b5"))
    )
    (comp (ref "R50")
      (value "4.7k")
      (footprint "FP-RN73R2A-IPC_C")
      (description "C17673")
      (libsource (lib "Altium Content Vault") (part "1029c3af85768c4190bb7ad29bc67b5"))
    )
    (comp (ref "R51")
      (value "20k 0805")
      (footprint "FP-RN73R2A-IPC_C")
      (description "C4328")
      (libsource (lib "Altium Content Vault") (part "1029c3af85768c4190bb7ad29bc67b5"))
    )
    (comp (ref "R52")
      (value "330 0805")
      (footprint "FP-RN73R2A-IPC_C")
      (description "C17630")
      (libsource (lib "Altium Content Vault") (part "1029c3af85768c4190bb7ad29bc67b5"))
    )
    (comp (ref "R53")
      (value "330 0805")
      (footprint "FP-RN73R2A-IPC_C")
      (description "C17630")
      (libsource (lib "Altium Content Vault") (part "1029c3af85768c4190bb7ad29bc67b5"))
    )
    (comp (ref "R54")
      (value "0ohm")
      (footprint "FP-HCJ1206-MFG")
      (description "C17888")
      (libsource (lib "Altium Content Vault") (part "1029c3af85768c4190bb7ad29bc67b5"))
    )
    (comp (ref "R55")
      (value "0ohm")
      (footprint "FP-HCJ1206-MFG")
      (description "C17888")
      (libsource (lib "Altium Content Vault") (part "1029c3af85768c4190bb7ad29bc67b5"))
    )
    (comp (ref "R56")
      (value "0ohm 0805")
      (footprint "FP-HCJ0805-MFG")
      (description "C17477")
      (libsource (lib "Altium Content Vault") (part "1029c3af85768c4190bb7ad29bc67b5"))
    )
    (comp (ref "R57")
      (value "330 0805")
      (footprint "FP-RN73R2A-IPC_C")
      (description "C17630")
      (libsource (lib "Altium Content Vault") (part "1029c3af85768c4190bb7ad29bc67b5"))
    )
    (comp (ref "R58")
      (value "0ohm")
      (footprint "FP-HCJ1206-MFG")
      (description "C17888")
      (libsource (lib "Altium Content Vault") (part "1029c3af85768c4190bb7ad29bc67b5"))
    )
    (comp (ref "R59")
      (value "1k 0805")
      (footprint "FP-RN73R2A-IPC_C")
      (description "C1015")
      (libsource (lib "Altium Content Vault") (part "1029c3af85768c4190bb7ad29bc67b5"))
    )
    (comp (ref "R60")
      (value "330 0805")
      (footprint "FP-RN73R2A-IPC_C")
      (description "C17630")
      (libsource (lib "Altium Content Vault") (part "1029c3af85768c4190bb7ad29bc67b5"))
    )
    (comp (ref "R61")
      (value "0ohm")
      (footprint "FP-HCJ1206-MFG")
      (description "C17888")
      (libsource (lib "Altium Content Vault") (part "1029c3af85768c4190bb7ad29bc67b5"))
    )
    (comp (ref "R62")
      (value "10k 0805")
      (footprint "FP-RN73R2A-IPC_C")
      (description "C17414")
      (libsource (lib "Altium Content Vault") (part "1029c3af85768c4190bb7ad29bc67b5"))
    )
    (comp (ref "R63")
      (value "0ohm 0805")
      (footprint "FP-HCJ0805-MFG")
      (description "C17477")
      (libsource (lib "Altium Content Vault") (part "1029c3af85768c4190bb7ad29bc67b5"))
    )
    (comp (ref "R64")
      (value "0ohm")
      (footprint "FP-HCJ1206-MFG")
      (description "C17888")
      (libsource (lib "Altium Content Vault") (part "1029c3af85768c4190bb7ad29bc67b5"))
    )
    (comp (ref "R65")
      (value "330 0805")
      (footprint "FP-RN73R2A-IPC_C")
      (description "C17630")
      (libsource (lib "Altium Content Vault") (part "1029c3af85768c4190bb7ad29bc67b5"))
    )
    (comp (ref "R66")
      (value "0ohm")
      (footprint "FP-HCJ1206-MFG")
      (description "C17888")
      (libsource (lib "Altium Content Vault") (part "1029c3af85768c4190bb7ad29bc67b5"))
    )
    (comp (ref "RNTC1")
      (value "100KOHM 0805")
      (footprint "FP-NCP21-0_2-IPC_A")
      (description "C338605")
      (fields (field (name "TOLERANCE") "5%"))
      (libsource (lib "Altium Content Vault") (part "3b148a6ebabc5fb4d708a66c052d352"))
    )
    (comp (ref "RT1")
      (value "NXRT15XH103FA1B030")
      (footprint "PcbLib1:THERM_NXRT15XH103FA1B030")
      (description "THERMISTOR NTC 10KOHM 3380K BEAD")
      (fields (field (name "MF") "Murata"))
      (libsource (lib "Schlib1") (part "NXRT15XH103FA1B030"))
    )
    (comp (ref "S1")
      (value "RP_Boot_Select")
      (footprint "SamacSys:TS1088AR02016")
      (description "C720477")
      (fields (field (name "MANUFACTURER_PART_NUMBER") "TS-1088-AR02016"))
      (libsource (lib "*") (part "TS-1088-AR02016"))
    )
    (comp (ref "S2")
      (value "ESP_Reset")
      (footprint "SamacSys:TS1088AR02016")
      (description "C720477")
      (fields (field (name "MANUFACTURER_PART_NUMBER") "TS-1088-AR02016"))
      (libsource (lib "*") (part "TS-1088-AR02016"))
    )
    (comp (ref "S3")
      (value "RP_Reset")
      (footprint "SamacSys:TS1088AR02016")
      (description "C720477")
      (fields (field (name "MANUFACTURER_PART_NUMBER") "TS-1088-AR02016"))
      (libsource (lib "") (part "TS-1088-AR02016_1"))
    )
    (comp (ref "S4")
      (value "ESP_Boot_select")
      (footprint "SamacSys:TS1088AR02016")
      (description "C720477")
      (fields (field (name "MANUFACTURER_PART_NUMBER") "TS-1088-AR02016"))
      (libsource (lib "*") (part "TS-1088-AR02016"))
    )
    (comp (ref "SW1")
      (value "DPDT Switch (fast charging siwtch, select for )")
      (footprint "PCBComponent_1 - duplicate")
      (description "C2848931")
      (fields (field (name "MANUFACTURER") "G-Switch(品赞)") (field (name "MANUFACTURER PART") "SS-22F32-G060"))
      (libsource (lib "Schlib1") (part "SS-22F32-G060"))
    )
    (comp (ref "SW2")
      (value "DPDT Switch (fast charging siwtch, select for )")
      (footprint "PCBComponent_1 - duplicate")
      (description "C2848931")
      (fields (field (name "MANUFACTURER") "G-Switch(品赞)") (field (name "MANUFACTURER PART") "SS-22F32-G060"))
      (libsource (lib "Schlib1") (part "SS-22F32-G060"))
    )
    (comp (ref "U1")
      (value "BMS")
      (footprint "MSOP-10_L3.0-W3.0-P0.50-LS4.9-BL - duplicate")
      (description "C22446437")
      (fields (field (name "MANUFACTURER") "iCM(创芯微)") (field (name "MANUFACTURER PART") "CM1022-CA"))
      (libsource (lib "Schlib1") (part "CM1022-CA"))
    )
    (comp (ref "U2")
      (value "Cell balancing")
      (footprint "SON65P300X300X100-9N")
      (description "C139352")
      (fields (field (name "MF") "Texas Instruments") (field (name "MP") "BQ29209DRBR"))
      (libsource (lib "Schlib1") (part "BQ29209DRBR"))
    )
    (comp (ref "Y1")
      (value "12Mhz Crystal")
      (footprint "SamacSys:ABM8272T3")
      (description "C20625731")
      (fields
        (field (name "MANUFACTURER_PART_NUMBER") "ABM8-272-T3")
        (field (name "MOUSER PART NUMBER") "815-ABM8-272-T3")
      )
      (libsource (lib "*") (part "ABM8-272-T3"))
    )
  )
  (nets
    (net (code "1") (name "+3V3") (class "Default")
      (node (ref "C10") (pin "2") (pinfunction "2_2") (pintype "passive"))
      (node (ref "C18") (pin "1") (pinfunction "1_1") (pintype "passive"))
      (node (ref "C22") (pin "1") (pinfunction "1_1") (pintype "passive"))
      (node (ref "C23") (pin "1") (pinfunction "1_1") (pintype "passive"))
      (node (ref "C24") (pin "1") (pinfunction "1_1") (pintype "passive"))
      (node (ref "C25") (pin "1") (pinfunction "1_1") (pintype "passive"))
      (node (ref "C26") (pin "1") (pinfunction "1_1") (pintype "passive"))
      (node (ref "C27") (pin "1") (pinfunction "1_1") (pintype "passive"))
      (node (ref "C28") (pin "1") (pinfunction "1_1") (pintype "passive"))
      (node (ref "C29") (pin "1") (pinfunction "1_1") (pintype "passive"))
      (node (ref "C3") (pin "1") (pinfunction "1_1") (pintype "passive"))
      (node (ref "C33") (pin "1") (pinfunction "1_1") (pintype "passive"))
      (node (ref "C34") (pin "1") (pinfunction "1_1") (pintype "passive"))
      (node (ref "C6") (pin "1") (pinfunction "1_1") (pintype "passive"))
      (node (ref "C9") (pin "2") (pinfunction "2_2") (pintype "passive"))
      (node (ref "IC1") (pin "20") (pinfunction "VCC_20") (pintype "passive"))
      (node (ref "IC2") (pin "8") (pinfunction "VCC_8") (pintype "passive"))
      (node (ref "IC4") (pin "1") (pinfunction "3V3_1") (pintype "passive"))
      (node (ref "J10") (pin "3") (pinfunction "3_3") (pintype "passive"))
      (node (ref "J6") (pin "1") (pinfunction "IOVDD_1_1") (pintype "passive"))
      (node (ref "J6") (pin "10") (pinfunction "IOVDD_2_10") (pintype "passive"))
      (node (ref "J6") (pin "22") (pinfunction "IOVDD_3_22") (pintype "passive"))
      (node (ref "J6") (pin "33") (pinfunction "IOVDD_4_33") (pintype "passive"))
      (node (ref "J6") (pin "42") (pinfunction "IOVDD_5_42") (pintype "passive"))
      (node (ref "J6") (pin "43") (pinfunction "ADC_AVDD_43") (pintype "passive"))
      (node (ref "J6") (pin "44") (pinfunction "VREG_VIN_44") (pintype "passive"))
      (node (ref "J6") (pin "48") (pinfunction "USB_VDD_48") (pintype "passive"))
      (node (ref "J6") (pin "49") (pinfunction "IOVDD_6_49") (pintype "passive"))
      (node (ref "J7") (pin "1") (pinfunction "1_1") (pintype "passive"))
      (node (ref "J7") (pin "2") (pinfunction "2_2") (pintype "passive"))
      (node (ref "J7") (pin "3") (pinfunction "3_3") (pintype "passive"))
      (node (ref "L1") (pin "2") (pinfunction "2_2") (pintype "passive"))
      (node (ref "R11") (pin "1") (pinfunction "1_1") (pintype "passive"))
      (node (ref "R19") (pin "2") (pinfunction "2_2") (pintype "passive"))
      (node (ref "R31") (pin "1") (pinfunction "1_1") (pintype "passive"))
      (node (ref "R32") (pin "2") (pinfunction "2_2") (pintype "passive"))
      (node (ref "R33") (pin "1") (pinfunction "1_1") (pintype "passive"))
      (node (ref "R35") (pin "1") (pinfunction "1_1") (pintype "passive"))
      (node (ref "R39") (pin "1") (pinfunction "1_1") (pintype "passive"))
      (node (ref "R49") (pin "1") (pinfunction "1_1") (pintype "passive"))
      (node (ref "R50") (pin "1") (pinfunction "1_1") (pintype "passive"))
      (node (ref "R54") (pin "2") (pinfunction "2_2") (pintype "passive"))
      (node (ref "R55") (pin "2") (pinfunction "2_2") (pintype "passive"))
      (node (ref "R58") (pin "2") (pinfunction "2_2") (pintype "passive"))
      (node (ref "R61") (pin "2") (pinfunction "2_2") (pintype "passive"))
      (node (ref "R64") (pin "2") (pinfunction "2_2") (pintype "passive"))
      (node (ref "R66") (pin "2") (pinfunction "2_2") (pintype "passive"))
      (node (ref "R9") (pin "1") (pinfunction "1_1") (pintype "passive"))
    )
    (net (code "2") (name "+5_Charging") (class "Default")
      (node (ref "C43") (pin "1") (pinfunction "1_1") (pintype "passive"))
      (node (ref "C44") (pin "1") (pinfunction "1_1") (pintype "passive"))
      (node (ref "IC5") (pin "16") (pinfunction "SVIN_16") (pintype "passive"))
      (node (ref "L2") (pin "2") (pinfunction "2_2") (pintype "passive"))
      (node (ref "R38") (pin "2") (pinfunction "2_2") (pintype "passive"))
      (node (ref "R59") (pin "2") (pinfunction "2_2") (pintype "passive"))
      (node (ref "R62") (pin "2") (pinfunction "2_2") (pintype "passive"))
      (node (ref "R63") (pin "1") (pinfunction "1_1") (pintype "passive"))
      (node (ref "SW1") (pin "4") (pinfunction "4_4") (pintype "passive"))
      (node (ref "SW2") (pin "5") (pinfunction "5_5") (pintype "passive"))
    )
    (net (code "3") (name "+5_preswitch") (class "Default")
      (node (ref "J1") (pin "A4_B9") (pinfunction "VBUS_A4_B9") (pintype "power_in"))
      (node (ref "J1") (pin "A9_B4") (pinfunction "VBUS_A9_B4") (pintype "power_in"))
      (node (ref "J2") (pin "A4_B9") (pinfunction "VBUS_A4_B9") (pintype "power_in"))
      (node (ref "J2") (pin "A9_B4") (pinfunction "VBUS_A9_B4") (pintype "power_in"))
      (node (ref "SW2") (pin "4") (pinfunction "4_4") (pintype "passive"))
    )
    (net (code "4") (name "/A01") (class "Default")
      (node (ref "IC1") (pin "1") (pinfunction "AO1_1_1") (pintype "passive"))
      (node (ref "IC1") (pin "2") (pinfunction "AO1_2_2") (pintype "passive"))
      (node (ref "J12") (pin "2") (pinfunction "2_2") (pintype "passive"))
    )
    (net (code "5") (name "/A02") (class "Default")
      (node (ref "IC1") (pin "5") (pinfunction "AO2_1_5") (pintype "passive"))
      (node (ref "IC1") (pin "6") (pinfunction "AO2_2_6") (pintype "passive"))
      (node (ref "J12") (pin "3") (pinfunction "3_3") (pintype "passive"))
    )
    (net (code "6") (name "/B01") (class "Default")
      (node (ref "IC1") (pin "11") (pinfunction "BO1_1_11") (pintype "passive"))
      (node (ref "IC1") (pin "12") (pinfunction "BO1_2_12") (pintype "passive"))
      (node (ref "J18") (pin "3") (pinfunction "3_3") (pintype "passive"))
    )
    (net (code "7") (name "/B02") (class "Default")
      (node (ref "IC1") (pin "7") (pinfunction "BO2_1_7") (pintype "passive"))
      (node (ref "IC1") (pin "8") (pinfunction "BO2_2_8") (pintype "passive"))
      (node (ref "J18") (pin "2") (pinfunction "2_2") (pintype "passive"))
    )
    (net (code "8") (name "/BOOT_ESP32") (class "Default")
      (node (ref "IC4") (pin "8") (pinfunction "IO9_8") (pintype "passive"))
      (node (ref "Q4") (pin "3") (pinfunction "C_3") (pintype "passive"))
      (node (ref "R39") (pin "2") (pinfunction "2_2") (pintype "passive"))
      (node (ref "S4") (pin "2") (pinfunction "NO_2") (pintype "passive"))
    )
    (net (code "9") (name "/Black_1") (class "Default")
      (node (ref "J15") (pin "1") (pinfunction "1_1") (pintype "passive"))
      (node (ref "J6") (pin "37") (pinfunction "GPIO25_37") (pintype "passive"))
    )
    (net (code "10") (name "/Black_2") (class "Default")
      (node (ref "J22") (pin "1") (pinfunction "1_1") (pintype "passive"))
      (node (ref "J6") (pin "32") (pinfunction "GPIO21_32") (pintype "passive"))
    )
    (net (code "11") (name "/Charging Select") (class "Default")
      (node (ref "IC5") (pin "9") (pinfunction "ICHG_9") (pintype "passive"))
      (node (ref "SW1") (pin "2") (pinfunction "2_2") (pintype "passive"))
    )
    (net (code "12") (name "/ESP_CC1") (class "Default")
      (node (ref "J1") (pin "A5") (pinfunction "CC1_A5") (pintype "bidirectional"))
      (node (ref "R1") (pin "1") (pinfunction "1_1") (pintype "passive"))
    )
    (net (code "13") (name "/ESP_CC2") (class "Default")
      (node (ref "J1") (pin "B5") (pinfunction "CC2_B5") (pintype "bidirectional"))
      (node (ref "R3") (pin "1") (pinfunction "1_1") (pintype "passive"))
    )
    (net (code "14") (name "/ESP_RX") (class "Default")
      (node (ref "IC4") (pin "11") (pinfunction "RXD_11") (pintype "passive"))
      (node (ref "J6") (pin "2") (pinfunction "GPIO0_2") (pintype "passive"))
    )
    (net (code "15") (name "/ESP_TX") (class "Default")
      (node (ref "IC4") (pin "12") (pinfunction "TXD_12") (pintype "passive"))
      (node (ref "J6") (pin "3") (pinfunction "GPIO1_3") (pintype "passive"))
    )
    (net (code "16") (name "/ESP_USB_D_N") (class "Default")
      (node (ref "D4") (pin "1") (pinfunction "IO_1_1") (pintype "passive"))
      (node (ref "IC4") (pin "13") (pinfunction "IO18_13") (pintype "passive"))
      (node (ref "J1") (pin "A7") (pinfunction "DN1_A7") (pintype "bidirectional"))
      (node (ref "J1") (pin "B7") (pinfunction "DN2_B7") (pintype "bidirectional"))
    )
    (net (code "17") (name "/ESP_USB_D_P") (class "Default")
      (node (ref "D2") (pin "1") (pinfunction "IO_1_1") (pintype "passive"))
      (node (ref "IC4") (pin "14") (pinfunction "IO19_14") (pintype "passive"))
      (node (ref "J1") (pin "A6") (pinfunction "DP1_A6") (pintype "bidirectional"))
      (node (ref "J1") (pin "B6") (pinfunction "DP2_B6") (pintype "bidirectional"))
    )
    (net (code "18") (name "/Enable_Charger") (class "Default")
      (node (ref "IC5") (pin "7") (pinfunction "EN_7") (pintype "passive"))
      (node (ref "Q5") (pin "3") (pinfunction "C_3") (pintype "passive"))
      (node (ref "R38") (pin "1") (pinfunction "1_1") (pintype "passive"))
    )
    (net (code "19") (name "/Enable_ESP32") (class "Default")
      (node (ref "C30") (pin "1") (pinfunction "1_1") (pintype "passive"))
      (node (ref "IC4") (pin "2") (pinfunction "EN_2") (pintype "passive"))
      (node (ref "Q3") (pin "3") (pinfunction "C_3") (pintype "passive"))
      (node (ref "R33") (pin "2") (pinfunction "2_2") (pintype "passive"))
      (node (ref "S2") (pin "2") (pinfunction "NO_2") (pintype "passive"))
    )
    (net (code "20") (name "/GP2") (class "Default")
      (node (ref "J20") (pin "2") (pinfunction "2_2") (pintype "passive"))
      (node (ref "J6") (pin "4") (pinfunction "GPIO2_4") (pintype "passive"))
      (node (ref "R5") (pin "1") (pinfunction "1_1") (pintype "passive"))
    )
    (net (code "21") (name "/GP3") (class "Default")
      (node (ref "IC1") (pin "22") (pinfunction "AIN2_22") (pintype "passive"))
      (node (ref "J6") (pin "5") (pinfunction "GPIO3_5") (pintype "passive"))
    )
    (net (code "22") (name "/GP4") (class "Default")
      (node (ref "IC1") (pin "21") (pinfunction "AIN1_21") (pintype "passive"))
      (node (ref "J6") (pin "6") (pinfunction "GPIO4_6") (pintype "passive"))
    )
    (net (code "23") (name "/GP5") (class "Default")
      (node (ref "IC1") (pin "19") (pinfunction "STBY_19") (pintype "passive"))
      (node (ref "J6") (pin "7") (pinfunction "GPIO5_7") (pintype "passive"))
    )
    (net (code "24") (name "/GP6") (class "Default")
      (node (ref "IC1") (pin "17") (pinfunction "BIN1_17") (pintype "passive"))
      (node (ref "J6") (pin "8") (pinfunction "GPIO6_8") (pintype "passive"))
    )
    (net (code "25") (name "/GP7") (class "Default")
      (node (ref "IC1") (pin "16") (pinfunction "BIN2_16") (pintype "passive"))
      (node (ref "J6") (pin "9") (pinfunction "GPIO7_9") (pintype "passive"))
    )
    (net (code "26") (name "/GP8") (class "Default")
      (node (ref "J20") (pin "3") (pinfunction "3_3") (pintype "passive"))
      (node (ref "J6") (pin "11") (pinfunction "GPIO8_11") (pintype "passive"))
      (node (ref "R8") (pin "1") (pinfunction "1_1") (pintype "passive"))
    )
    (net (code "27") (name "/GP9") (class "Default")
      (node (ref "J6") (pin "12") (pinfunction "GPIO9_12") (pintype "passive"))
    )
    (net (code "28") (name "/GP10") (class "Default")
      (node (ref "J6") (pin "13") (pinfunction "GPIO10_13") (pintype "passive"))
    )
    (net (code "29") (name "/GP11") (class "Default")
      (node (ref "J10") (pin "2") (pinfunction "2_2") (pintype "passive"))
      (node (ref "R29") (pin "2") (pinfunction "2_2") (pintype "passive"))
      (node (ref "R50") (pin "2") (pinfunction "2_2") (pintype "passive"))
    )
    (net (code "30") (name "/GP12") (class "Default")
      (node (ref "J10") (pin "1") (pinfunction "1_1") (pintype "passive"))
      (node (ref "R36") (pin "2") (pinfunction "2_2") (pintype "passive"))
      (node (ref "R49") (pin "2") (pinfunction "2_2") (pintype "passive"))
    )
    (net (code "31") (name "/GP13") (class "Default")
      (node (ref "J6") (pin "16") (pinfunction "GPIO13_16") (pintype "passive"))
    )
    (net (code "32") (name "/GP14") (class "Default")
      (node (ref "J6") (pin "17") (pinfunction "GPIO14_17") (pintype "passive"))
    )
    (net (code "33") (name "/GP15") (class "Default")
      (node (ref "J6") (pin "18") (pinfunction "GPIO15_18") (pintype "passive"))
      (node (ref "R26") (pin "2") (pinfunction "2_2") (pintype "passive"))
    )
    (net (code "34") (name "/GP16") (class "Default")
      (node (ref "J6") (pin "27") (pinfunction "GPIO16_27") (pintype "passive"))
      (node (ref "R30") (pin "1") (pinfunction "1_1") (pintype "passive"))
    )
    (net (code "35") (name "/GP17") (class "Default")
      (node (ref "J6") (pin "28") (pinfunction "GPIO17_28") (pintype "passive"))
      (node (ref "R41") (pin "1") (pinfunction "1_1") (pintype "passive"))
    )
    (net (code "36") (name "/GP26_ADC") (class "Default")
      (node (ref "J6") (pin "38") (pinfunction "GPIO26_/_ADC0_38") (pintype "passive"))
    )
    (net (code "37") (name "/GP27_ADC") (class "Default")
      (node (ref "J6") (pin "39") (pinfunction "GPIO27_/_ADC1_39") (pintype "passive"))
      (node (ref "J8") (pin "1") (pinfunction "1_1") (pintype "passive"))
    )
    (net (code "38") (name "/GP28_ADC") (class "Default")
      (node (ref "J6") (pin "40") (pinfunction "GPIO28_/_ADC2_40") (pintype "passive"))
      (node (ref "J8") (pin "2") (pinfunction "2_2") (pintype "passive"))
    )
    (net (code "39") (name "/GP29_ADC") (class "Default")
      (node (ref "J6") (pin "41") (pinfunction "GPIO29_/_ADC3_41") (pintype "passive"))
      (node (ref "J8") (pin "3") (pinfunction "3_3") (pintype "passive"))
    )
    (net (code "40") (name "/IO2") (class "Default")
      (node (ref "IC4") (pin "16") (pinfunction "IO2_16") (pintype "passive"))
      (node (ref "R31") (pin "2") (pinfunction "2_2") (pintype "passive"))
    )
    (net (code "41") (name "/IO8") (class "Default")
      (node (ref "IC4") (pin "7") (pinfunction "IO8_7") (pintype "passive"))
      (node (ref "R32") (pin "1") (pinfunction "1_1") (pintype "passive"))
    )
    (net (code "42") (name "/LED(G1)") (class "Default")
      (node (ref "J14") (pin "2") (pinfunction "2_2") (pintype "passive"))
      (node (ref "R60") (pin "2") (pinfunction "2_2") (pintype "passive"))
      (node (ref "R64") (pin "1") (pinfunction "1_1") (pintype "passive"))
    )
    (net (code "43") (name "/LED(G2)") (class "Default")
      (node (ref "J14") (pin "1") (pinfunction "1_1") (pintype "passive"))
      (node (ref "R65") (pin "2") (pinfunction "2_2") (pintype "passive"))
      (node (ref "R66") (pin "1") (pinfunction "1_1") (pintype "passive"))
    )
    (net (code "44") (name "/LED(Green)") (class "Default")
      (node (ref "J9") (pin "2") (pinfunction "2_2") (pintype "passive"))
      (node (ref "R52") (pin "2") (pinfunction "2_2") (pintype "passive"))
      (node (ref "R55") (pin "1") (pinfunction "1_1") (pintype "passive"))
    )
    (net (code "45") (name "/LED(Red)") (class "Default")
      (node (ref "J14") (pin "3") (pinfunction "3_3") (pintype "passive"))
      (node (ref "R57") (pin "2") (pinfunction "2_2") (pintype "passive"))
      (node (ref "R61") (pin "1") (pinfunction "1_1") (pintype "passive"))
    )
    (net (code "46") (name "/LED(White)") (class "Default")
      (node (ref "J9") (pin "3") (pinfunction "3_3") (pintype "passive"))
      (node (ref "R47") (pin "2") (pinfunction "2_2") (pintype "passive"))
      (node (ref "R54") (pin "1") (pinfunction "1_1") (pintype "passive"))
    )
    (net (code "47") (name "/LED(Yellow)") (class "Default")
      (node (ref "J9") (pin "1") (pinfunction "1_1") (pintype "passive"))
      (node (ref "R53") (pin "2") (pinfunction "2_2") (pintype "passive"))
      (node (ref "R58") (pin "1") (pinfunction "1_1") (pintype "passive"))
    )
    (net (code "48") (name "/NTC") (class "Default")
      (node (ref "IC5") (pin "4") (pinfunction "NTC_4") (pintype "passive"))
      (node (ref "J20") (pin "1") (pinfunction "1_1") (pintype "passive"))
      (node (ref "R56") (pin "2") (pinfunction "2_2") (pintype "passive"))
      (node (ref "R63") (pin "2") (pinfunction "2_2") (pintype "passive"))
    )
    (net (code "49") (name "/Orange_1") (class "Default")
      (node (ref "J15") (pin "3") (pinfunction "3_3") (pintype "passive"))
      (node (ref "J6") (pin "35") (pinfunction "GPIO23_35") (pintype "passive"))
    )
    (net (code "50") (name "/Orange_2") (class "Default")
      (node (ref "J22") (pin "3") (pinfunction "3_3") (pintype "passive"))
      (node (ref "J6") (pin "30") (pinfunction "GPIO19_30") (pintype "passive"))
    )
    (net (code "51") (name "/Out") (class "Default")
      (node (ref "R42") (pin "1") (pinfunction "1_1") (pintype "passive"))
      (node (ref "U2") (pin "8") (pinfunction "OUT_8") (pintype "output"))
    )
    (net (code "52") (name "/PWMA") (class "Default")
      (node (ref "IC1") (pin "23") (pinfunction "PWMA_23") (pintype "passive"))
      (node (ref "J21") (pin "2") (pinfunction "2_2") (pintype "passive"))
      (node (ref "R5") (pin "2") (pinfunction "2_2") (pintype "passive"))
    )
    (net (code "53") (name "/PWMB") (class "Default")
      (node (ref "IC1") (pin "15") (pinfunction "PWMB_15") (pintype "passive"))
      (node (ref "J21") (pin "1") (pinfunction "1_1") (pintype "passive"))
      (node (ref "R8") (pin "2") (pinfunction "2_2") (pintype "passive"))
    )
    (net (code "54") (name "/QSPI_CS") (class "Default")
      (node (ref "IC2") (pin "1") (pinfunction "~{CS}_1") (pintype "passive"))
      (node (ref "J6") (pin "56") (pinfunction "QSPI_SS_N_56") (pintype "passive"))
      (node (ref "R9") (pin "2") (pinfunction "2_2") (pintype "passive"))
      (node (ref "S1") (pin "2") (pinfunction "NO_2") (pintype "passive"))
    )
    (net (code "55") (name "/QSPI_SCLK") (class "Default")
      (node (ref "IC2") (pin "6") (pinfunction "CLK_6") (pintype "passive"))
      (node (ref "J6") (pin "52") (pinfunction "QSPI_SCLK_52") (pintype "passive"))
    )
    (net (code "56") (name "/QSPI_SD0") (class "Default")
      (node (ref "IC2") (pin "5") (pinfunction "DI_(IO0)_5") (pintype "passive"))
      (node (ref "J6") (pin "53") (pinfunction "QSPI_SD0_53") (pintype "passive"))
    )
    (net (code "57") (name "/QSPI_SD1") (class "Default")
      (node (ref "IC2") (pin "2") (pinfunction "DO_(IO1)_2") (pintype "passive"))
      (node (ref "J6") (pin "55") (pinfunction "QSPI_SD1_55") (pintype "passive"))
    )
    (net (code "58") (name "/QSPI_SD2") (class "Default")
      (node (ref "IC2") (pin "3") (pinfunction "~{WP_(IO2)}_3") (pintype "passive"))
      (node (ref "J6") (pin "54") (pinfunction "QSPI_SD2_54") (pintype "passive"))
    )
    (net (code "59") (name "/QSPI_SD3") (class "Default")
      (node (ref "IC2") (pin "7") (pinfunction "~{HOLD_OR_}/RESET_(IO3)_7") (pintype "passive"))
      (node (ref "J6") (pin "51") (pinfunction "QSPI_SD3_51") (pintype "passive"))
    )
    (net (code "60") (name "/RP_CC1") (class "Default")
      (node (ref "J2") (pin "A5") (pinfunction "CC1_A5") (pintype "bidirectional"))
      (node (ref "R2") (pin "1") (pinfunction "1_1") (pintype "passive"))
    )
    (net (code "61") (name "/RP_CC2") (class "Default")
      (node (ref "J2") (pin "B5") (pinfunction "CC2_B5") (pintype "bidirectional"))
      (node (ref "R4") (pin "1") (pinfunction "1_1") (pintype "passive"))
    )
    (net (code "62") (name "/RP_USB_D_N") (class "Default")
      (node (ref "D5") (pin "1") (pinfunction "IO_1_1") (pintype "passive"))
      (node (ref "J2") (pin "A7") (pinfunction "DN1_A7") (pintype "bidirectional"))
      (node (ref "J2") (pin "B7") (pinfunction "DN2_B7") (pintype "bidirectional"))
      (node (ref "J6") (pin "46") (pinfunction "USB_DM_46") (pintype "passive"))
    )
    (net (code "63") (name "/RP_USB_D_P") (class "Default")
      (node (ref "D3") (pin "1") (pinfunction "IO_1_1") (pintype "passive"))
      (node (ref "J2") (pin "A6") (pinfunction "DP1_A6") (pintype "bidirectional"))
      (node (ref "J2") (pin "B6") (pinfunction "DP2_B6") (pintype "bidirectional"))
      (node (ref "J6") (pin "47") (pinfunction "USB_DP_47") (pintype "passive"))
    )
    (net (code "64") (name "/Red_1") (class "Default")
      (node (ref "J15") (pin "2") (pinfunction "2_2") (pintype "passive"))
      (node (ref "J6") (pin "36") (pinfunction "GPIO24_36") (pintype "passive"))
    )
    (net (code "65") (name "/Red_2") (class "Default")
      (node (ref "J22") (pin "2") (pinfunction "2_2") (pintype "passive"))
      (node (ref "J6") (pin "31") (pinfunction "GPIO20_31") (pintype "passive"))
    )
    (net (code "66") (name "/SWCK") (class "Default")
      (node (ref "J19") (pin "1") (pinfunction "1_1") (pintype "passive"))
      (node (ref "J6") (pin "24") (pinfunction "SWCLK_24") (pintype "passive"))
    )
    (net (code "67") (name "/SWDO") (class "Default")
      (node (ref "J19") (pin "3") (pinfunction "3_3") (pintype "passive"))
      (node (ref "J6") (pin "25") (pinfunction "SWDIO_25") (pintype "passive"))
    )
    (net (code "68") (name "/TCK") (class "Default")
      (node (ref "IC4") (pin "5") (pinfunction "IO6_5") (pintype "passive"))
      (node (ref "J16") (pin "2") (pinfunction "2_2") (pintype "passive"))
    )
    (net (code "69") (name "/TDI") (class "Default")
      (node (ref "IC4") (pin "4") (pinfunction "IO5_4") (pintype "passive"))
      (node (ref "J16") (pin "3") (pinfunction "3_3") (pintype "passive"))
    )
    (net (code "70") (name "/TDO") (class "Default")
      (node (ref "IC4") (pin "6") (pinfunction "IO7_6") (pintype "passive"))
      (node (ref "J16") (pin "1") (pinfunction "1_1") (pintype "passive"))
    )
    (net (code "71") (name "/TMS") (class "Default")
      (node (ref "IC4") (pin "3") (pinfunction "IO4_3") (pintype "passive"))
      (node (ref "J16") (pin "4") (pinfunction "4_4") (pintype "passive"))
    )
    (net (code "72") (name "/Temp") (class "Default")
      (node (ref "J21") (pin "3") (pinfunction "3_3") (pintype "passive"))
      (node (ref "R56") (pin "1") (pinfunction "1_1") (pintype "passive"))
      (node (ref "R62") (pin "1") (pinfunction "1_1") (pintype "passive"))
      (node (ref "RT1") (pin "2") (pinfunction "2_2") (pintype "passive"))
    )
    (net (code "73") (name "/Yellow_1") (class "Default")
      (node (ref "J12") (pin "1") (pinfunction "1_1") (pintype "passive"))
      (node (ref "J6") (pin "34") (pinfunction "GPIO22_34") (pintype "passive"))
    )
    (net (code "74") (name "/Yellow_2") (class "Default")
      (node (ref "J18") (pin "1") (pinfunction "1_1") (pintype "passive"))
      (node (ref "J6") (pin "29") (pinfunction "GPIO18_29") (pintype "passive"))
    )
    (net (code "75") (name "1V1") (class "Default")
      (node (ref "C17") (pin "1") (pinfunction "1_1") (pintype "passive"))
      (node (ref "C19") (pin "1") (pinfunction "1_1") (pintype "passive"))
      (node (ref "C20") (pin "1") (pinfunction "1_1") (pintype "passive"))
      (node (ref "J6") (pin "23") (pinfunction "DVDD_1_23") (pintype "passive"))
      (node (ref "J6") (pin "45") (pinfunction "VREG_VOUT_45") (pintype "passive"))
      (node (ref "J6") (pin "50") (pinfunction "DVDD_2_50") (pintype "passive"))
    )
    (net (code "76") (name "Bat+") (class "Default")
      (node (ref "C1") (pin "2") (pinfunction "A_2") (pintype "passive"))
      (node (ref "C2") (pin "1") (pinfunction "1_1") (pintype "passive"))
      (node (ref "D1") (pin "1") (pinfunction "K_1") (pintype "passive"))
      (node (ref "IC1") (pin "13") (pinfunction "VM2_13") (pintype "passive"))
      (node (ref "IC1") (pin "14") (pinfunction "VM3_14") (pintype "passive"))
      (node (ref "IC1") (pin "24") (pinfunction "VM1_24") (pintype "passive"))
      (node (ref "IC5") (pin "12") (pinfunction "BAT_12") (pintype "passive"))
      (node (ref "SW1") (pin "6") (pinfunction "6_6") (pintype "passive"))
      (node (ref "SW2") (pin "2") (pinfunction "2_2") (pintype "passive"))
    )
    (net (code "77") (name "Bat+_Preswitch") (class "Default")
      (node (ref "J5") (pin "3") (pinfunction "3_3") (pintype "passive"))
      (node (ref "R10") (pin "1") (pinfunction "1_1") (pintype "passive"))
      (node (ref "R37") (pin "1") (pinfunction "1_1") (pintype "passive"))
      (node (ref "R45") (pin "1") (pinfunction "1_1") (pintype "passive"))
      (node (ref "SW2") (pin "3") (pinfunction "3_3") (pintype "passive"))
    )
    (net (code "78") (name "Bat-") (class "Default")
      (node (ref "C11") (pin "2") (pinfunction "2_2") (pintype "passive"))
      (node (ref "C32") (pin "2") (pinfunction "2_2") (pintype "passive"))
      (node (ref "C37") (pin "1") (pinfunction "1_1") (pintype "passive"))
      (node (ref "C39") (pin "2") (pinfunction "2_2") (pintype "passive"))
      (node (ref "C7") (pin "2") (pinfunction "2_2") (pintype "passive"))
      (node (ref "J5") (pin "1") (pinfunction "1_1") (pintype "passive"))
      (node (ref "R27") (pin "1") (pinfunction "1_1") (pintype "passive"))
      (node (ref "R28") (pin "1") (pinfunction "1_1") (pintype "passive"))
      (node (ref "RNTC1") (pin "1") (pinfunction "1_1") (pintype "passive"))
      (node (ref "U1") (pin "3") (pinfunction "VSS_3") (pintype "passive"))
      (node (ref "U2") (pin "5") (pinfunction "GND_5") (pintype "power_in"))
      (node (ref "U2") (pin "6") (pinfunction "~{CB_EN}_6") (pintype "input"))
      (node (ref "U2") (pin "9") (pinfunction "EXP_9") (pintype "power_in"))
    )
    (net (code "79") (name "GND") (class "Default")
      (node (ref "C1") (pin "1") (pinfunction "C_1") (pintype "passive"))
      (node (ref "C10") (pin "1") (pinfunction "1_1") (pintype "passive"))
      (node (ref "C12") (pin "2") (pinfunction "2_2") (pintype "passive"))
      (node (ref "C13") (pin "2") (pinfunction "2_2") (pintype "passive"))
      (node (ref "C14") (pin "2") (pinfunction "2_2") (pintype "passive"))
      (node (ref "C16") (pin "2") (pinfunction "2_2") (pintype "passive"))
      (node (ref "C17") (pin "2") (pinfunction "2_2") (pintype "passive"))
      (node (ref "C18") (pin "2") (pinfunction "2_2") (pintype "passive"))
      (node (ref "C19") (pin "2") (pinfunction "2_2") (pintype "passive"))
      (node (ref "C2") (pin "2") (pinfunction "2_2") (pintype "passive"))
      (node (ref "C20") (pin "2") (pinfunction "2_2") (pintype "passive"))
      (node (ref "C21") (pin "2") (pinfunction "2_2") (pintype "passive"))
      (node (ref "C22") (pin "2") (pinfunction "2_2") (pintype "passive"))
      (node (ref "C23") (pin "2") (pinfunction "2_2") (pintype "passive"))
      (node (ref "C24") (pin "2") (pinfunction "2_2") (pintype "passive"))
      (node (ref "C25") (pin "2") (pinfunction "2_2") (pintype "passive"))
      (node (ref "C26") (pin "2") (pinfunction "2_2") (pintype "passive"))
      (node (ref "C27") (pin "2") (pinfunction "2_2") (pintype "passive"))
      (node (ref "C28") (pin "2") (pinfunction "2_2") (pintype "passive"))
      (node (ref "C29") (pin "2") (pinfunction "2_2") (pintype "passive"))
      (node (ref "C3") (pin "2") (pinfunction "2_2") (pintype "passive"))
      (node (ref "C30") (pin "2") (pinfunction "2_2") (pintype "passive"))
      (node (ref "C31") (pin "2") (pinfunction "2_2") (pintype "passive"))
      (node (ref "C33") (pin "2") (pinfunction "2_2") (pintype "passive"))
      (node (ref "C34") (pin "2") (pinfunction "2_2") (pintype "passive"))
      (node (ref "C35") (pin "2") (pinfunction "2_2") (pintype "passive"))
      (node (ref "C36") (pin "2") (pinfunction "2_2") (pintype "passive"))
      (node (ref "C4") (pin "1") (pinfunction "1_1") (pintype "passive"))
      (node (ref "C40") (pin "2") (pinfunction "2_2") (pintype "passive"))
      (node (ref "C41") (pin "2") (pinfunction "2_2") (pintype "passive"))
      (node (ref "C43") (pin "2") (pinfunction "2_2") (pintype "passive"))
      (node (ref "C44") (pin "2") (pinfunction "2_2") (pintype "passive"))
      (node (ref "C5") (pin "1") (pinfunction "1_1") (pintype "passive"))
      (node (ref "C6") (pin "2") (pinfunction "2_2") (pintype "passive"))
      (node (ref "C9") (pin "1") (pinfunction "1_1") (pintype "passive"))
      (node (ref "D1") (pin "2") (pinfunction "A_2") (pintype "passive"))
      (node (ref "D2") (pin "2") (pinfunction "IO_2_2") (pintype "passive"))
      (node (ref "D3") (pin "2") (pinfunction "IO_2_2") (pintype "passive"))
      (node (ref "D4") (pin "2") (pinfunction "IO_2_2") (pintype "passive"))
      (node (ref "D5") (pin "2") (pinfunction "IO_2_2") (pintype "passive"))
      (node (ref "D6") (pin "2") (pinfunction "A_2") (pintype "passive"))
      (node (ref "IC1") (pin "10") (pinfunction "PGND2_2_10") (pintype "passive"))
      (node (ref "IC1") (pin "18") (pinfunction "GND_18") (pintype "passive"))
      (node (ref "IC1") (pin "3") (pinfunction "PGND1_1_3") (pintype "passive"))
      (node (ref "IC1") (pin "4") (pinfunction "PGND1_2_4") (pintype "passive"))
      (node (ref "IC1") (pin "9") (pinfunction "PGND2_1_9") (pintype "passive"))
      (node (ref "IC2") (pin "4") (pinfunction "GND_4") (pintype "passive"))
      (node (ref "IC3") (pin "7") (pinfunction "GND_7") (pintype "passive"))
      (node (ref "IC4") (pin "19") (pinfunction "GND_2_19") (pintype "passive"))
      (node (ref "IC4") (pin "20") (pinfunction "GND_3_20") (pintype "passive"))
      (node (ref "IC4") (pin "21") (pinfunction "GND_4_21") (pintype "passive"))
      (node (ref "IC4") (pin "22") (pinfunction "GND_5_22") (pintype "passive"))
      (node (ref "IC4") (pin "23") (pinfunction "GND_6_23") (pintype "passive"))
      (node (ref "IC4") (pin "24") (pinfunction "GND_7_24") (pintype "passive"))
      (node (ref "IC4") (pin "25") (pinfunction "GND_8_25") (pintype "passive"))
      (node (ref "IC4") (pin "26") (pinfunction "GND_9_26") (pintype "passive"))
      (node (ref "IC4") (pin "27") (pinfunction "GND_10_27") (pintype "passive"))
      (node (ref "IC4") (pin "9") (pinfunction "GND_1_9") (pintype "passive"))
      (node (ref "IC5") (pin "15") (pinfunction "PGND_15") (pintype "passive"))
      (node (ref "IC5") (pin "5") (pinfunction "CV_5") (pintype "passive"))
      (node (ref "IC5") (pin "8") (pinfunction "SGND_8") (pintype "passive"))
      (node (ref "J1") (pin "A12_B1") (pinfunction "GND_A12_B1") (pintype "power_in"))
      (node (ref "J1") (pin "A1_B12") (pinfunction "GND_A1_B12") (pintype "power_in"))
      (node (ref "J10") (pin "4") (pinfunction "4_4") (pintype "passive"))
      (node (ref "J11") (pin "1") (pinfunction "1_1") (pintype "passive"))
      (node (ref "J11") (pin "2") (pinfunction "2_2") (pintype "passive"))
      (node (ref "J11") (pin "3") (pinfunction "3_3") (pintype "passive"))
      (node (ref "J13") (pin "1") (pinfunction "1_1") (pintype "passive"))
      (node (ref "J13") (pin "2") (pinfunction "2_2") (pintype "passive"))
      (node (ref "J13") (pin "3") (pinfunction "3_3") (pintype "passive"))
      (node (ref "J19") (pin "2") (pinfunction "2_2") (pintype "passive"))
      (node (ref "J2") (pin "A12_B1") (pinfunction "GND_A12_B1") (pintype "power_in"))
      (node (ref "J2") (pin "A1_B12") (pinfunction "GND_A1_B12") (pintype "power_in"))
      (node (ref "J6") (pin "19") (pinfunction "TESTEN_19") (pintype "passive"))
      (node (ref "J6") (pin "57") (pinfunction "GND_57") (pintype "passive"))
      (node (ref "LED1") (pin "2") (pinfunction "K_2") (pintype "passive"))
      (node (ref "LED10") (pin "2") (pinfunction "K_2") (pintype "passive"))
      (node (ref "LED2") (pin "1") (pinfunction "K_1") (pintype "passive"))
      (node (ref "LED3") (pin "2") (pinfunction "K_2") (pintype "passive"))
      (node (ref "LED4") (pin "2") (pinfunction "K_2") (pintype "passive"))
      (node (ref "LED5") (pin "2") (pinfunction "K_2") (pintype "passive"))
      (node (ref "LED6") (pin "2") (pinfunction "K_2") (pintype "passive"))
      (node (ref "LED8") (pin "1") (pinfunction "K_1") (pintype "passive"))
      (node (ref "LED9") (pin "2") (pinfunction "K_2") (pintype "passive"))
      (node (ref "Q2") (pin "2") (pinfunction "S_2") (pintype "passive"))
      (node (ref "Q3") (pin "2") (pinfunction "E_2") (pintype "passive"))
      (node (ref "Q4") (pin "2") (pinfunction "E_2") (pintype "passive"))
      (node (ref "Q5") (pin "2") (pinfunction "E_2") (pintype "passive"))
      (node (ref "R1") (pin "2") (pinfunction "2_2") (pintype "passive"))
      (node (ref "R15") (pin "1") (pinfunction "1_1") (pintype "passive"))
      (node (ref "R16") (pin "2") (pinfunction "2_2") (pintype "passive"))
      (node (ref "R17") (pin "1") (pinfunction "1_1") (pintype "passive"))
      (node (ref "R2") (pin "2") (pinfunction "2_2") (pintype "passive"))
      (node (ref "R20") (pin "2") (pinfunction "2_2") (pintype "passive"))
      (node (ref "R21") (pin "2") (pinfunction "2_2") (pintype "passive"))
      (node (ref "R3") (pin "2") (pinfunction "2_2") (pintype "passive"))
      (node (ref "R34") (pin "1") (pinfunction "1_1") (pintype "passive"))
      (node (ref "R4") (pin "2") (pinfunction "2_2") (pintype "passive"))
      (node (ref "R43") (pin "1") (pinfunction "1_1") (pintype "passive"))
      (node (ref "R48") (pin "1") (pinfunction "1_1") (pintype "passive"))
      (node (ref "R51") (pin "1") (pinfunction "1_1") (pintype "passive"))
      (node (ref "R6") (pin "1") (pinfunction "1_1") (pintype "passive"))
      (node (ref "R7") (pin "1") (pinfunction "1_1") (pintype "passive"))
      (node (ref "RT1") (pin "1") (pinfunction "1_1") (pintype "passive"))
      (node (ref "S2") (pin "1") (pinfunction "COM_1") (pintype "passive"))
      (node (ref "S3") (pin "2") (pinfunction "NO_2") (pintype "passive"))
      (node (ref "S4") (pin "1") (pinfunction "COM_1") (pintype "passive"))
      (node (ref "Y1") (pin "2") (pinfunction "GND_1_2") (pintype "passive"))
      (node (ref "Y1") (pin "4") (pinfunction "GND_2_4") (pintype "passive"))
    )
    (net (code "80") (name "Midtap") (class "Default")
      (node (ref "J5") (pin "2") (pinfunction "2_2") (pintype "passive"))
      (node (ref "R12") (pin "1") (pinfunction "1_1") (pintype "passive"))
      (node (ref "R44") (pin "1") (pinfunction "1_1") (pintype "passive"))
      (node (ref "R46") (pin "1") (pinfunction "1_1") (pintype "passive"))
    )
    (net (code "81") (name "Net-(C4-Pad2)") (class "Default")
      (node (ref "C4") (pin "2") (pinfunction "2_2") (pintype "passive"))
      (node (ref "J1") (pin "SH1") (pinfunction "SHIELD_SH1") (pintype "passive"))
      (node (ref "J1") (pin "SH2") (pinfunction "SHIELD_SH2") (pintype "passive"))
      (node (ref "J1") (pin "SH3") (pinfunction "SHIELD_SH3") (pintype "passive"))
      (node (ref "J1") (pin "SH4") (pinfunction "SHIELD_SH4") (pintype "passive"))
      (node (ref "R6") (pin "2") (pinfunction "2_2") (pintype "passive"))
    )
    (net (code "82") (name "Net-(C5-Pad2)") (class "Default")
      (node (ref "C5") (pin "2") (pinfunction "2_2") (pintype "passive"))
      (node (ref "J2") (pin "SH1") (pinfunction "SHIELD_SH1") (pintype "passive"))
      (node (ref "J2") (pin "SH2") (pinfunction "SHIELD_SH2") (pintype "passive"))
      (node (ref "J2") (pin "SH3") (pinfunction "SHIELD_SH3") (pintype "passive"))
      (node (ref "J2") (pin "SH4") (pinfunction "SHIELD_SH4") (pintype "passive"))
      (node (ref "R7") (pin "2") (pinfunction "2_2") (pintype "passive"))
    )
    (net (code "83") (name "Net-(C15-Pad2)") (class "Default")
      (node (ref "C15") (pin "2") (pinfunction "2_2") (pintype "passive"))
      (node (ref "R16") (pin "1") (pinfunction "1_1") (pintype "passive"))
    )
    (net (code "84") (name "Net-(D6-K)") (class "Default")
      (node (ref "C8") (pin "1") (pinfunction "1_1") (pintype "passive"))
      (node (ref "D6") (pin "1") (pinfunction "K_1") (pintype "passive"))
      (node (ref "IC3") (pin "8") (pinfunction "PH_8") (pintype "passive"))
      (node (ref "L1") (pin "1") (pinfunction "1_1") (pintype "passive"))
    )
    (net (code "85") (name "Net-(IC3-BOOT)") (class "Default")
      (node (ref "C8") (pin "2") (pinfunction "2_2") (pintype "passive"))
      (node (ref "IC3") (pin "1") (pinfunction "BOOT_1") (pintype "passive"))
    )
    (net (code "86") (name "Net-(IC3-COMP)") (class "Default")
      (node (ref "C15") (pin "1") (pinfunction "1_1") (pintype "passive"))
      (node (ref "C16") (pin "1") (pinfunction "1_1") (pintype "passive"))
      (node (ref "IC3") (pin "6") (pinfunction "COMP_6") (pintype "passive"))
    )
    (net (code "87") (name "Net-(IC3-EN)") (class "Default")
      (node (ref "IC3") (pin "3") (pinfunction "EN_3") (pintype "passive"))
      (node (ref "R14") (pin "2") (pinfunction "2_2") (pintype "passive"))
      (node (ref "R20") (pin "1") (pinfunction "1_1") (pintype "passive"))
    )
    (net (code "88") (name "Net-(IC3-SS)") (class "Default")
      (node (ref "C21") (pin "1") (pinfunction "1_1") (pintype "passive"))
      (node (ref "IC3") (pin "4") (pinfunction "SS_4") (pintype "passive"))
    )
    (net (code "89") (name "Net-(IC3-VSENSE)") (class "Default")
      (node (ref "IC3") (pin "5") (pinfunction "VSENSE_5") (pintype "passive"))
      (node (ref "R13") (pin "2") (pinfunction "2_2") (pintype "passive"))
      (node (ref "R21") (pin "1") (pinfunction "1_1") (pintype "passive"))
    )
    (net (code "90") (name "Net-(IC5-BD_1)") (class "Default")
      (node (ref "C40") (pin "1") (pinfunction "1_1") (pintype "passive"))
      (node (ref "IC5") (pin "10") (pinfunction "BD_1_10") (pintype "passive"))
      (node (ref "IC5") (pin "13") (pinfunction "BD_2_13") (pintype "passive"))
    )
    (net (code "91") (name "Net-(IC5-BST)") (class "Default")
      (node (ref "C42") (pin "1") (pinfunction "1_1") (pintype "passive"))
      (node (ref "IC5") (pin "11") (pinfunction "BST_11") (pintype "passive"))
    )
    (net (code "92") (name "Net-(IC5-LX)") (class "Default")
      (node (ref "C42") (pin "2") (pinfunction "2_2") (pintype "passive"))
      (node (ref "IC5") (pin "14") (pinfunction "LX_14") (pintype "passive"))
      (node (ref "L2") (pin "1") (pinfunction "1_1") (pintype "passive"))
    )
    (net (code "93") (name "Net-(IC5-STAT)") (class "Default")
      (node (ref "IC5") (pin "1") (pinfunction "STAT_1") (pintype "passive"))
      (node (ref "LED7") (pin "2") (pinfunction "K_2") (pintype "passive"))
    )
    (net (code "94") (name "Net-(IC5-TIM)") (class "Default")
      (node (ref "C41") (pin "1") (pinfunction "1_1") (pintype "passive"))
      (node (ref "IC5") (pin "3") (pinfunction "TIM_3") (pintype "passive"))
    )
    (net (code "95") (name "Net-(J6-GPIO11)") (class "Default")
      (node (ref "J6") (pin "14") (pinfunction "GPIO11_14") (pintype "passive"))
      (node (ref "R29") (pin "1") (pinfunction "1_1") (pintype "passive"))
    )
    (net (code "96") (name "Net-(J6-GPIO12)") (class "Default")
      (node (ref "J6") (pin "15") (pinfunction "GPIO12_15") (pintype "passive"))
      (node (ref "R36") (pin "1") (pinfunction "1_1") (pintype "passive"))
    )
    (net (code "97") (name "Net-(J6-RUN)") (class "Default")
      (node (ref "C31") (pin "1") (pinfunction "1_1") (pintype "passive"))
      (node (ref "J6") (pin "26") (pinfunction "RUN_26") (pintype "passive"))
      (node (ref "R35") (pin "2") (pinfunction "2_2") (pintype "passive"))
      (node (ref "S3") (pin "1") (pinfunction "COM_1") (pintype "passive"))
    )
    (net (code "98") (name "Net-(J6-XIN)") (class "Default")
      (node (ref "C36") (pin "1") (pinfunction "1_1") (pintype "passive"))
      (node (ref "J6") (pin "20") (pinfunction "XIN_20") (pintype "passive"))
      (node (ref "Y1") (pin "1") (pinfunction "CRYSTAL_1_1") (pintype "passive"))
    )
    (net (code "99") (name "Net-(J6-XOUT)") (class "Default")
      (node (ref "J6") (pin "21") (pinfunction "XOUT_21") (pintype "passive"))
      (node (ref "R40") (pin "1") (pinfunction "1_1") (pintype "passive"))
    )
    (net (code "100") (name "Net-(LED1-A)") (class "Default")
      (node (ref "LED1") (pin "1") (pinfunction "A_1") (pintype "passive"))
      (node (ref "R19") (pin "1") (pinfunction "1_1") (pintype "passive"))
    )
    (net (code "101") (name "Net-(LED2-A)") (class "Default")
      (node (ref "LED2") (pin "2") (pinfunction "A_2") (pintype "passive"))
      (node (ref "R24") (pin "2") (pinfunction "2_2") (pintype "passive"))
    )
    (net (code "102") (name "Net-(LED3-A)") (class "Default")
      (node (ref "LED3") (pin "1") (pinfunction "A_1") (pintype "passive"))
      (node (ref "R26") (pin "1") (pinfunction "1_1") (pintype "passive"))
    )
    (net (code "103") (name "Net-(LED4-A)") (class "Default")
      (node (ref "LED4") (pin "1") (pinfunction "A_1") (pintype "passive"))
      (node (ref "R47") (pin "1") (pinfunction "1_1") (pintype "passive"))
    )
    (net (code "104") (name "Net-(LED5-A)") (class "Default")
      (node (ref "LED5") (pin "1") (pinfunction "A_1") (pintype "passive"))
      (node (ref "R52") (pin "1") (pinfunction "1_1") (pintype "passive"))
    )
    (net (code "105") (name "Net-(LED6-A)") (class "Default")
      (node (ref "LED6") (pin "1") (pinfunction "A_1") (pintype "passive"))
      (node (ref "R53") (pin "1") (pinfunction "1_1") (pintype "passive"))
    )
    (net (code "106") (name "Net-(LED7-A)") (class "Default")
      (node (ref "LED7") (pin "1") (pinfunction "A_1") (pintype "passive"))
      (node (ref "R59") (pin "1") (pinfunction "1_1") (pintype "passive"))
    )
    (net (code "107") (name "Net-(LED8-A)") (class "Default")
      (node (ref "LED8") (pin "2") (pinfunction "A_2") (pintype "passive"))
      (node (ref "R57") (pin "1") (pinfunction "1_1") (pintype "passive"))
    )
    (net (code "108") (name "Net-(LED9-A)") (class "Default")
      (node (ref "LED9") (pin "1") (pinfunction "A_1") (pintype "passive"))
      (node (ref "R60") (pin "1") (pinfunction "1_1") (pintype "passive"))
    )
    (net (code "109") (name "Net-(LED10-A)") (class "Default")
      (node (ref "LED10") (pin "1") (pinfunction "A_1") (pintype "passive"))
      (node (ref "R65") (pin "1") (pinfunction "1_1") (pintype "passive"))
    )
    (net (code "110") (name "Net-(Q1-D)") (class "Default")
      (node (ref "Q1") (pin "3") (pinfunction "D_3") (pintype "passive"))
      (node (ref "Q2") (pin "3") (pinfunction "D_3") (pintype "passive"))
      (node (ref "R28") (pin "2") (pinfunction "2_2") (pintype "passive"))
    )
    (net (code "111") (name "Net-(Q1-G)") (class "Default")
      (node (ref "Q1") (pin "1") (pinfunction "G_1") (pintype "passive"))
      (node (ref "R22") (pin "1") (pinfunction "1_1") (pintype "passive"))
    )
    (net (code "112") (name "Net-(Q1-S)") (class "Default")
      (node (ref "Q1") (pin "2") (pinfunction "S_2") (pintype "passive"))
      (node (ref "R25") (pin "1") (pinfunction "1_1") (pintype "passive"))
      (node (ref "R27") (pin "2") (pinfunction "2_2") (pintype "passive"))
    )
    (net (code "113") (name "Net-(Q2-G)") (class "Default")
      (node (ref "Q2") (pin "1") (pinfunction "G_1") (pintype "passive"))
      (node (ref "R23") (pin "1") (pinfunction "1_1") (pintype "passive"))
    )
    (net (code "114") (name "Net-(Q3-B)") (class "Default")
      (node (ref "Q3") (pin "1") (pinfunction "B_1") (pintype "passive"))
      (node (ref "R30") (pin "2") (pinfunction "2_2") (pintype "passive"))
      (node (ref "R34") (pin "2") (pinfunction "2_2") (pintype "passive"))
    )
    (net (code "115") (name "Net-(Q4-B)") (class "Default")
      (node (ref "Q4") (pin "1") (pinfunction "B_1") (pintype "passive"))
      (node (ref "R41") (pin "2") (pinfunction "2_2") (pintype "passive"))
      (node (ref "R43") (pin "2") (pinfunction "2_2") (pintype "passive"))
    )
    (net (code "116") (name "Net-(Q5-B)") (class "Default")
      (node (ref "Q5") (pin "1") (pinfunction "B_1") (pintype "passive"))
      (node (ref "R42") (pin "2") (pinfunction "2_2") (pintype "passive"))
    )
    (net (code "117") (name "Net-(R11-Pad2)") (class "Default")
      (node (ref "R11") (pin "2") (pinfunction "2_2") (pintype "passive"))
      (node (ref "R13") (pin "1") (pinfunction "1_1") (pintype "passive"))
    )
    (net (code "118") (name "Net-(R48-Pad2)") (class "Default")
      (node (ref "R48") (pin "2") (pinfunction "2_2") (pintype "passive"))
      (node (ref "SW1") (pin "3") (pinfunction "3_3") (pintype "passive"))
    )
    (net (code "119") (name "Net-(R51-Pad2)") (class "Default")
      (node (ref "R51") (pin "2") (pinfunction "2_2") (pintype "passive"))
      (node (ref "SW1") (pin "1") (pinfunction "1_1") (pintype "passive"))
    )
    (net (code "120") (name "Net-(S1-COM)") (class "Default")
      (node (ref "R17") (pin "2") (pinfunction "2_2") (pintype "passive"))
      (node (ref "S1") (pin "1") (pinfunction "COM_1") (pintype "passive"))
    )
    (net (code "121") (name "Net-(U1-CO)") (class "Default")
      (node (ref "R23") (pin "2") (pinfunction "2_2") (pintype "passive"))
      (node (ref "U1") (pin "9") (pinfunction "CO_9") (pintype "passive"))
    )
    (net (code "122") (name "Net-(U1-DO)") (class "Default")
      (node (ref "R22") (pin "2") (pinfunction "2_2") (pintype "passive"))
      (node (ref "U1") (pin "8") (pinfunction "DO_8") (pintype "passive"))
    )
    (net (code "123") (name "Net-(U1-RTS)") (class "Default")
      (node (ref "R18") (pin "1") (pinfunction "1_1") (pintype "passive"))
      (node (ref "RNTC1") (pin "2") (pinfunction "2_2") (pintype "passive"))
      (node (ref "U1") (pin "5") (pinfunction "RTS_5") (pintype "passive"))
    )
    (net (code "124") (name "Net-(U1-RTV)") (class "Default")
      (node (ref "R18") (pin "2") (pinfunction "2_2") (pintype "passive"))
      (node (ref "U1") (pin "6") (pinfunction "RTV_6") (pintype "passive"))
    )
    (net (code "125") (name "Net-(U1-VC1)") (class "Default")
      (node (ref "C7") (pin "1") (pinfunction "1_1") (pintype "passive"))
      (node (ref "R10") (pin "2") (pinfunction "2_2") (pintype "passive"))
      (node (ref "U1") (pin "1") (pinfunction "VC1_1") (pintype "passive"))
    )
    (net (code "126") (name "Net-(U1-VC2)") (class "Default")
      (node (ref "C11") (pin "1") (pinfunction "1_1") (pintype "passive"))
      (node (ref "R12") (pin "2") (pinfunction "2_2") (pintype "passive"))
      (node (ref "U1") (pin "2") (pinfunction "VC2_2") (pintype "passive"))
    )
    (net (code "127") (name "Net-(U1-VIN)") (class "Default")
      (node (ref "R25") (pin "2") (pinfunction "2_2") (pintype "passive"))
      (node (ref "U1") (pin "7") (pinfunction "VIN_7") (pintype "passive"))
    )
    (net (code "128") (name "Net-(U1-VM)") (class "Default")
      (node (ref "R15") (pin "2") (pinfunction "2_2") (pintype "passive"))
      (node (ref "U1") (pin "10") (pinfunction "VM_10") (pintype "passive"))
    )
    (net (code "129") (name "Net-(U2-CD)") (class "Default")
      (node (ref "C39") (pin "1") (pinfunction "1_1") (pintype "passive"))
      (node (ref "U2") (pin "4") (pinfunction "CD_4") (pintype "passive"))
    )
    (net (code "130") (name "Net-(U2-VC1)") (class "Default")
      (node (ref "C37") (pin "2") (pinfunction "2_2") (pintype "passive"))
      (node (ref "C38") (pin "1") (pinfunction "1_1") (pintype "passive"))
      (node (ref "R44") (pin "2") (pinfunction "2_2") (pintype "passive"))
      (node (ref "U2") (pin "2") (pinfunction "VC1_2") (pintype "input"))
    )
    (net (code "131") (name "Net-(U2-VC1_CB)") (class "Default")
      (node (ref "R46") (pin "2") (pinfunction "2_2") (pintype "passive"))
      (node (ref "U2") (pin "3") (pinfunction "VC1_CB_3") (pintype "input"))
    )
    (net (code "132") (name "Net-(U2-VC2)") (class "Default")
      (node (ref "C38") (pin "2") (pinfunction "2_2") (pintype "passive"))
      (node (ref "R45") (pin "2") (pinfunction "2_2") (pintype "passive"))
      (node (ref "U2") (pin "1") (pinfunction "VC2_1") (pintype "input"))
    )
    (net (code "133") (name "Net-(U2-VDD)") (class "Default")
      (node (ref "C32") (pin "1") (pinfunction "1_1") (pintype "passive"))
      (node (ref "R37") (pin "2") (pinfunction "2_2") (pintype "passive"))
      (node (ref "U2") (pin "7") (pinfunction "VDD_7") (pintype "power_in"))
    )
    (net (code "134") (name "Net-(Y1-CRYSTAL_2)") (class "Default")
      (node (ref "C35") (pin "1") (pinfunction "1_1") (pintype "passive"))
      (node (ref "R40") (pin "2") (pinfunction "2_2") (pintype "passive"))
      (node (ref "Y1") (pin "3") (pinfunction "CRYSTAL_2_3") (pintype "passive"))
    )
    (net (code "135") (name "Vin_Buck") (class "Default")
      (node (ref "C12") (pin "1") (pinfunction "1_1") (pintype "passive"))
      (node (ref "C13") (pin "1") (pinfunction "1_1") (pintype "passive"))
      (node (ref "C14") (pin "1") (pinfunction "1_1") (pintype "passive"))
      (node (ref "IC3") (pin "2") (pinfunction "VIN_2") (pintype "passive"))
      (node (ref "J17") (pin "1") (pinfunction "1_1") (pintype "passive"))
      (node (ref "J17") (pin "2") (pinfunction "2_2") (pintype "passive"))
      (node (ref "J17") (pin "3") (pinfunction "3_3") (pintype "passive"))
      (node (ref "R14") (pin "1") (pinfunction "1_1") (pintype "passive"))
      (node (ref "R24") (pin "1") (pinfunction "1_1") (pintype "passive"))
      (node (ref "SW1") (pin "5") (pinfunction "5_5") (pintype "passive"))
    )
    (net (code "136") (name "unconnected-(IC4-IO0-Pad18)") (class "Default")
      (node (ref "IC4") (pin "18") (pinfunction "IO0_18") (pintype "passive"))
    )
    (net (code "137") (name "unconnected-(IC4-IO1-Pad17)") (class "Default")
      (node (ref "IC4") (pin "17") (pinfunction "IO1_17") (pintype "passive"))
    )
    (net (code "138") (name "unconnected-(IC4-IO3-Pad15)") (class "Default")
      (node (ref "IC4") (pin "15") (pinfunction "IO3_15") (pintype "passive"))
    )
    (net (code "139") (name "unconnected-(IC4-IO10-Pad10)") (class "Default")
      (node (ref "IC4") (pin "10") (pinfunction "IO10_10") (pintype "passive"))
    )
    (net (code "140") (name "unconnected-(IC5-ILIM-Pad6)") (class "Default")
      (node (ref "IC5") (pin "6") (pinfunction "ILIM_6") (pintype "passive+no_connect"))
    )
    (net (code "141") (name "unconnected-(IC5-SYSRT-Pad2)") (class "Default")
      (node (ref "IC5") (pin "2") (pinfunction "SYSRT_2") (pintype "passive+no_connect"))
    )
    (net (code "142") (name "unconnected-(J1-SBU1-PadA8)") (class "Default")
      (node (ref "J1") (pin "A8") (pinfunction "SBU1_A8") (pintype "bidirectional+no_connect"))
    )
    (net (code "143") (name "unconnected-(J1-SBU2-PadB8)") (class "Default")
      (node (ref "J1") (pin "B8") (pinfunction "SBU2_B8") (pintype "bidirectional+no_connect"))
    )
    (net (code "144") (name "unconnected-(J2-SBU1-PadA8)") (class "Default")
      (node (ref "J2") (pin "A8") (pinfunction "SBU1_A8") (pintype "bidirectional+no_connect"))
    )
    (net (code "145") (name "unconnected-(J2-SBU2-PadB8)") (class "Default")
      (node (ref "J2") (pin "B8") (pinfunction "SBU2_B8") (pintype "bidirectional+no_connect"))
    )
    (net (code "146") (name "unconnected-(SW2-Pad1)") (class "Default")
      (node (ref "SW2") (pin "1") (pinfunction "1_1") (pintype "passive"))
    )
    (net (code "147") (name "unconnected-(SW2-Pad6)") (class "Default")
      (node (ref "SW2") (pin "6") (pinfunction "6_6") (pintype "passive"))
    )
    (net (code "148") (name "unconnected-(U1-NC-Pad4)") (class "Default")
      (node (ref "U1") (pin "4") (pinfunction "NC_4") (pintype "passive+no_connect"))
    )
  )
)
